# das48.net
KiCad netlist of a schematic drawn in EAGLE
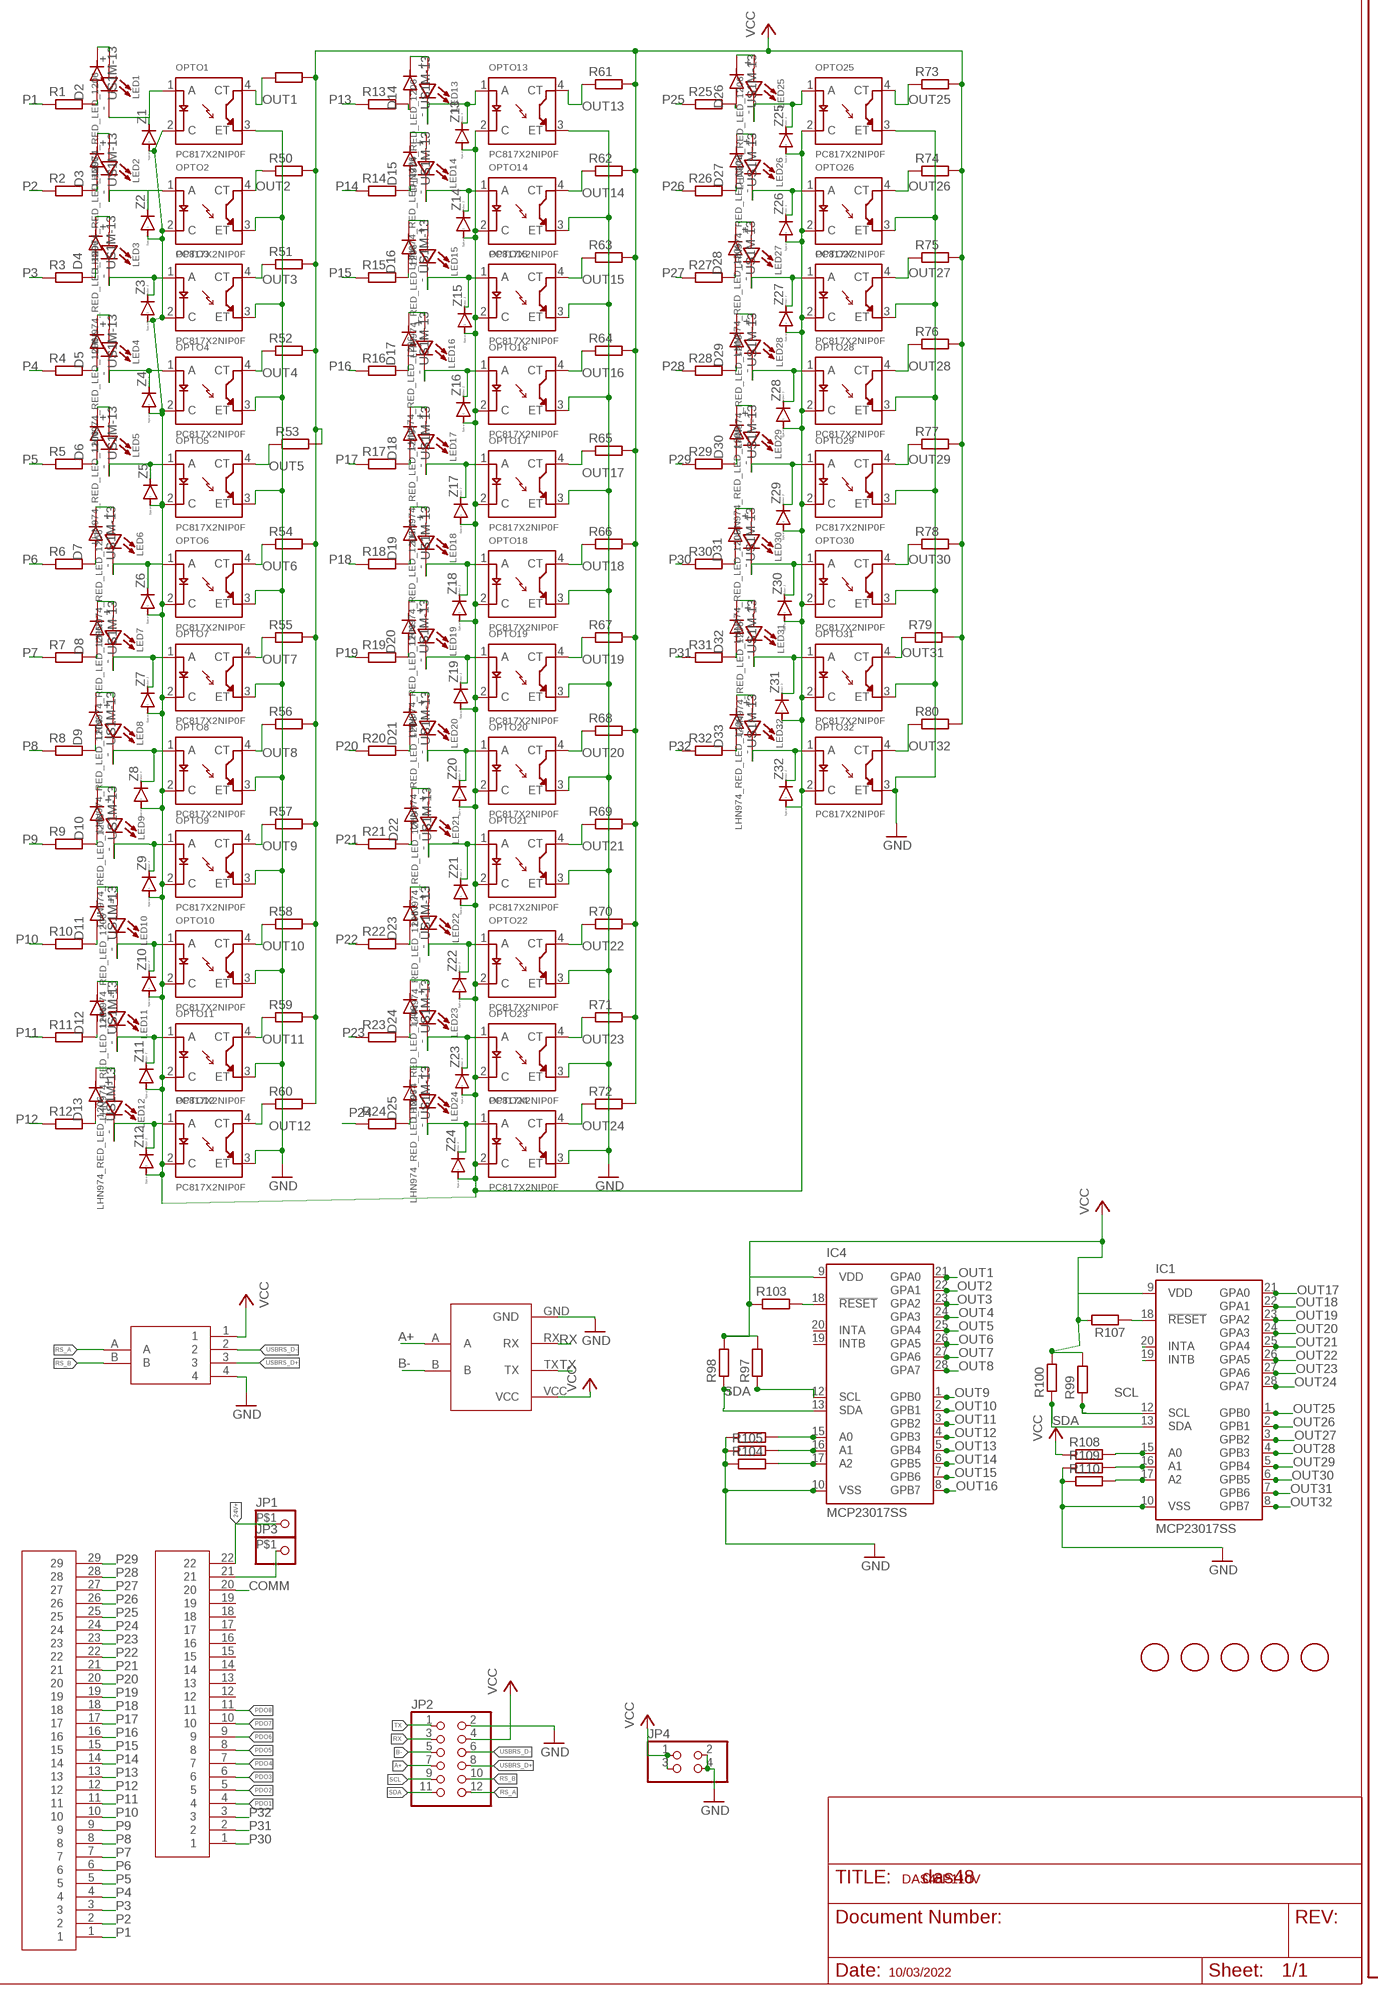
[diagram p0: schematic, sheet 1, part 1 of 2]
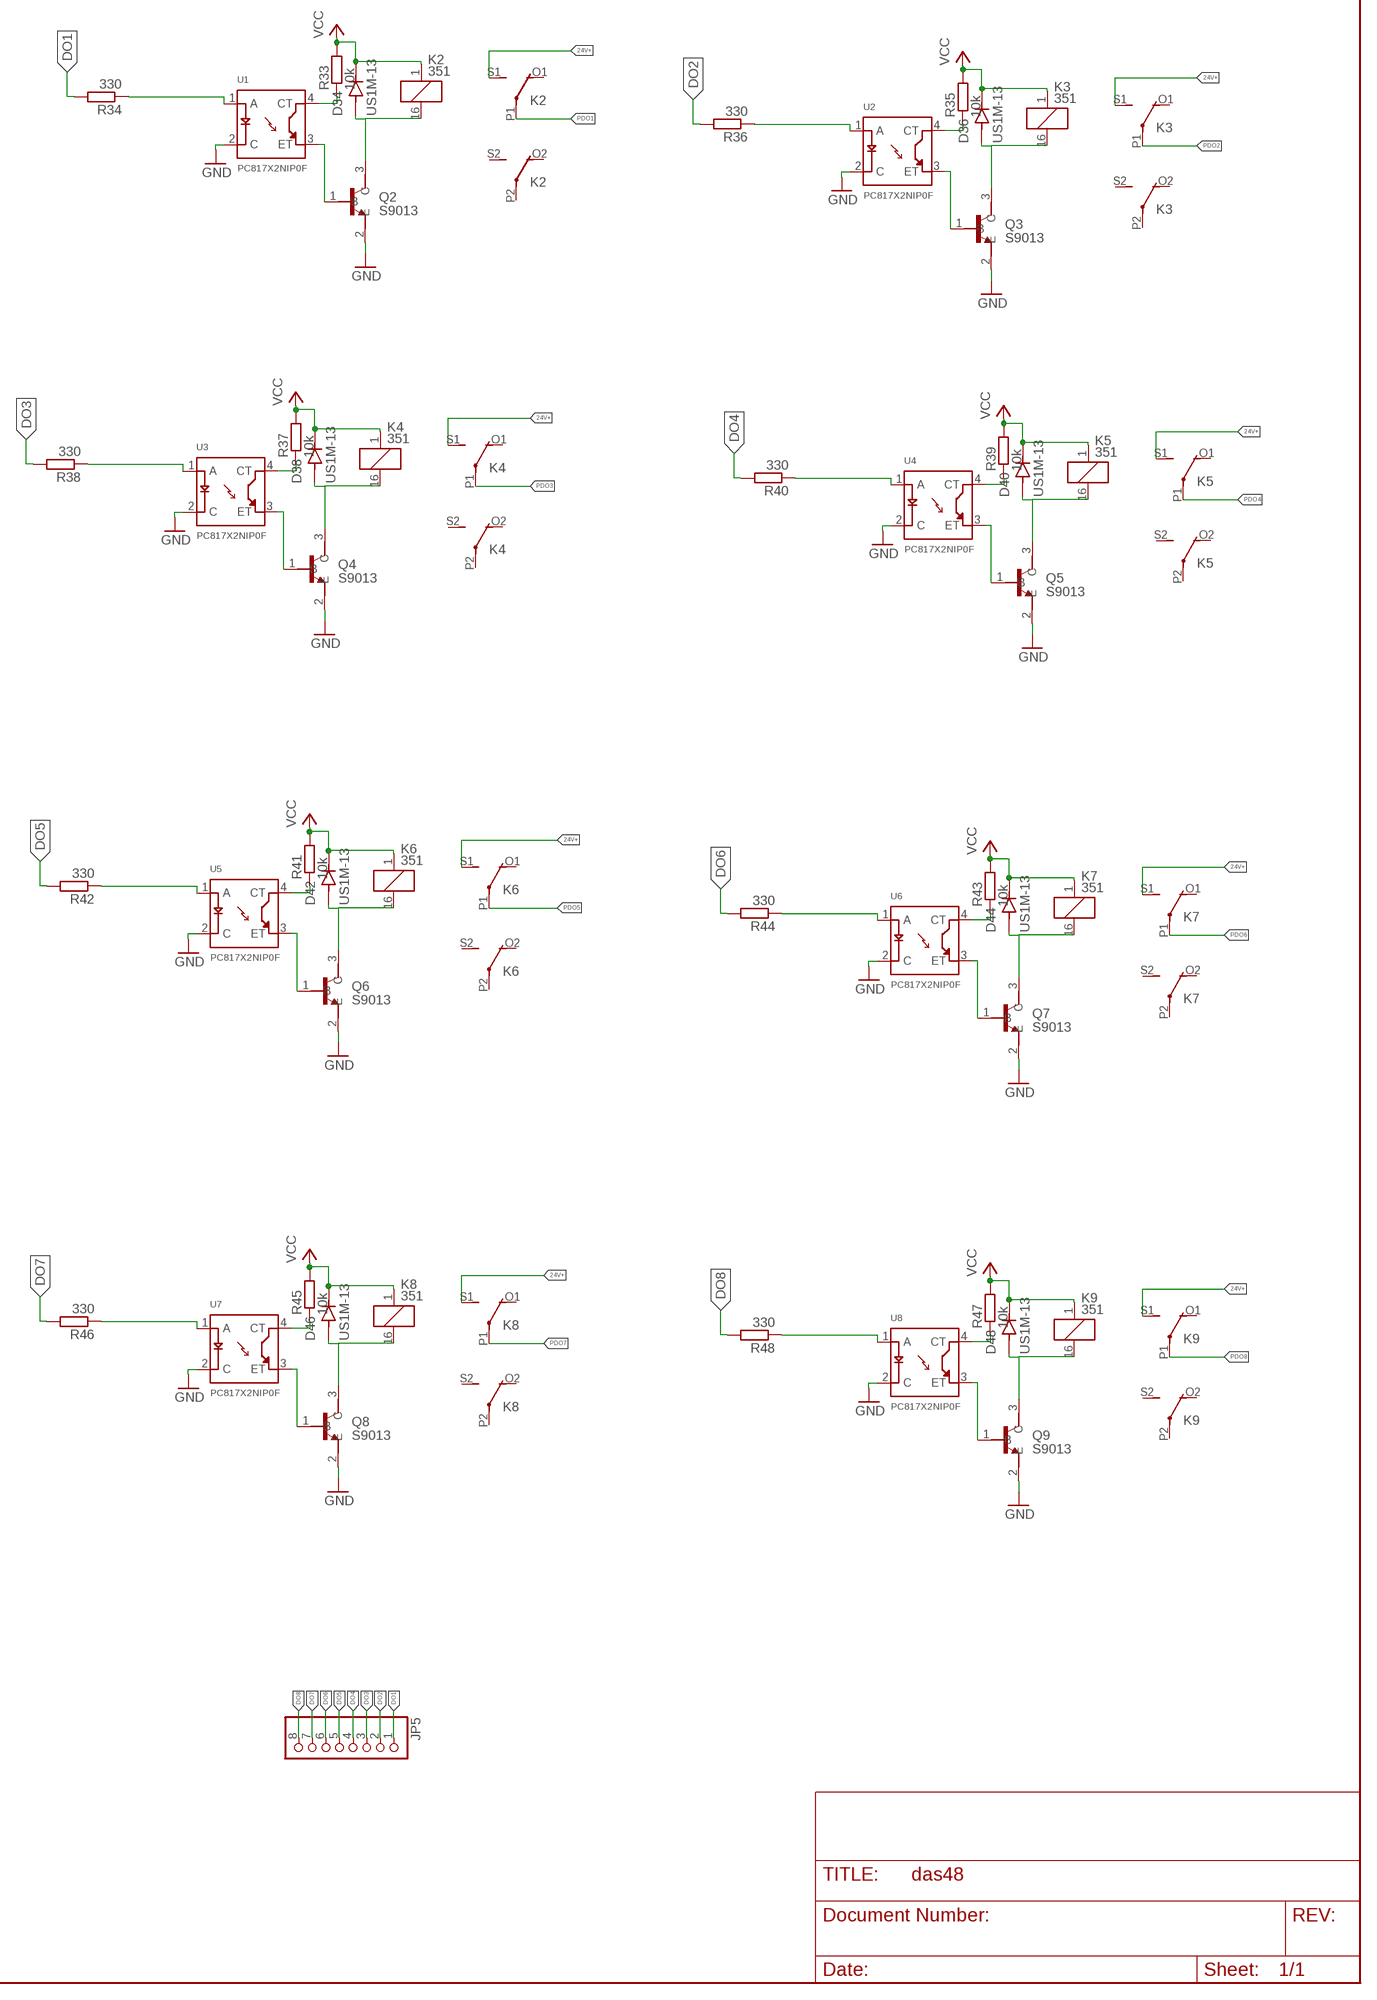
[diagram p1: schematic, sheet 1, part 2 of 2]

(export (version "E")
  (design (tool "Eeschema 10.0.6"))
  (components
    (comp (ref "D2")
      (value "US1M-13")
      (footprint "eagle-import:DIOM5226X240N")
      (fields (field (name "MF") "Diodes Incorporated"))
      (libsource (lib "eagle-import") (part "US1M-13"))
    )
    (comp (ref "D3")
      (value "US1M-13")
      (footprint "eagle-import:DIOM5226X240N")
      (fields (field (name "MF") "Diodes Incorporated"))
      (libsource (lib "eagle-import") (part "US1M-13"))
    )
    (comp (ref "D4")
      (value "US1M-13")
      (footprint "eagle-import:DIOM5226X240N")
      (fields (field (name "MF") "Diodes Incorporated"))
      (libsource (lib "eagle-import") (part "US1M-13"))
    )
    (comp (ref "D5")
      (value "US1M-13")
      (footprint "eagle-import:DIOM5226X240N")
      (fields (field (name "MF") "Diodes Incorporated"))
      (libsource (lib "eagle-import") (part "US1M-13"))
    )
    (comp (ref "D6")
      (value "US1M-13")
      (footprint "eagle-import:DIOM5226X240N")
      (fields (field (name "MF") "Diodes Incorporated"))
      (libsource (lib "eagle-import") (part "US1M-13"))
    )
    (comp (ref "D7")
      (value "US1M-13")
      (footprint "eagle-import:DIOM5226X240N")
      (fields (field (name "MF") "Diodes Incorporated"))
      (libsource (lib "eagle-import") (part "US1M-13"))
    )
    (comp (ref "D8")
      (value "US1M-13")
      (footprint "eagle-import:DIOM5226X240N")
      (fields (field (name "MF") "Diodes Incorporated"))
      (libsource (lib "eagle-import") (part "US1M-13"))
    )
    (comp (ref "D9")
      (value "US1M-13")
      (footprint "eagle-import:DIOM5226X240N")
      (fields (field (name "MF") "Diodes Incorporated"))
      (libsource (lib "eagle-import") (part "US1M-13"))
    )
    (comp (ref "D10")
      (value "US1M-13")
      (footprint "eagle-import:DIOM5226X240N")
      (fields (field (name "MF") "Diodes Incorporated"))
      (libsource (lib "eagle-import") (part "US1M-13"))
    )
    (comp (ref "D11")
      (value "US1M-13")
      (footprint "eagle-import:DIOM5226X240N")
      (fields (field (name "MF") "Diodes Incorporated"))
      (libsource (lib "eagle-import") (part "US1M-13"))
    )
    (comp (ref "D12")
      (value "US1M-13")
      (footprint "eagle-import:DIOM5226X240N")
      (fields (field (name "MF") "Diodes Incorporated"))
      (libsource (lib "eagle-import") (part "US1M-13"))
    )
    (comp (ref "D13")
      (value "US1M-13")
      (footprint "eagle-import:DIOM5226X240N")
      (fields (field (name "MF") "Diodes Incorporated"))
      (libsource (lib "eagle-import") (part "US1M-13"))
    )
    (comp (ref "D14")
      (value "US1M-13")
      (footprint "eagle-import:DIOM5226X240N")
      (fields (field (name "MF") "Diodes Incorporated"))
      (libsource (lib "eagle-import") (part "US1M-13"))
    )
    (comp (ref "D15")
      (value "US1M-13")
      (footprint "eagle-import:DIOM5226X240N")
      (fields (field (name "MF") "Diodes Incorporated"))
      (libsource (lib "eagle-import") (part "US1M-13"))
    )
    (comp (ref "D16")
      (value "US1M-13")
      (footprint "eagle-import:DIOM5226X240N")
      (fields (field (name "MF") "Diodes Incorporated"))
      (libsource (lib "eagle-import") (part "US1M-13"))
    )
    (comp (ref "D17")
      (value "US1M-13")
      (footprint "eagle-import:DIOM5226X240N")
      (fields (field (name "MF") "Diodes Incorporated"))
      (libsource (lib "eagle-import") (part "US1M-13"))
    )
    (comp (ref "D18")
      (value "US1M-13")
      (footprint "eagle-import:DIOM5226X240N")
      (fields (field (name "MF") "Diodes Incorporated"))
      (libsource (lib "eagle-import") (part "US1M-13"))
    )
    (comp (ref "D19")
      (value "US1M-13")
      (footprint "eagle-import:DIOM5226X240N")
      (fields (field (name "MF") "Diodes Incorporated"))
      (libsource (lib "eagle-import") (part "US1M-13"))
    )
    (comp (ref "D20")
      (value "US1M-13")
      (footprint "eagle-import:DIOM5226X240N")
      (fields (field (name "MF") "Diodes Incorporated"))
      (libsource (lib "eagle-import") (part "US1M-13"))
    )
    (comp (ref "D21")
      (value "US1M-13")
      (footprint "eagle-import:DIOM5226X240N")
      (fields (field (name "MF") "Diodes Incorporated"))
      (libsource (lib "eagle-import") (part "US1M-13"))
    )
    (comp (ref "D22")
      (value "US1M-13")
      (footprint "eagle-import:DIOM5226X240N")
      (fields (field (name "MF") "Diodes Incorporated"))
      (libsource (lib "eagle-import") (part "US1M-13"))
    )
    (comp (ref "D23")
      (value "US1M-13")
      (footprint "eagle-import:DIOM5226X240N")
      (fields (field (name "MF") "Diodes Incorporated"))
      (libsource (lib "eagle-import") (part "US1M-13"))
    )
    (comp (ref "D24")
      (value "US1M-13")
      (footprint "eagle-import:DIOM5226X240N")
      (fields (field (name "MF") "Diodes Incorporated"))
      (libsource (lib "eagle-import") (part "US1M-13"))
    )
    (comp (ref "D25")
      (value "US1M-13")
      (footprint "eagle-import:DIOM5226X240N")
      (fields (field (name "MF") "Diodes Incorporated"))
      (libsource (lib "eagle-import") (part "US1M-13"))
    )
    (comp (ref "D26")
      (value "US1M-13")
      (footprint "eagle-import:DIOM5226X240N")
      (fields (field (name "MF") "Diodes Incorporated"))
      (libsource (lib "eagle-import") (part "US1M-13"))
    )
    (comp (ref "D27")
      (value "US1M-13")
      (footprint "eagle-import:DIOM5226X240N")
      (fields (field (name "MF") "Diodes Incorporated"))
      (libsource (lib "eagle-import") (part "US1M-13"))
    )
    (comp (ref "D28")
      (value "US1M-13")
      (footprint "eagle-import:DIOM5226X240N")
      (fields (field (name "MF") "Diodes Incorporated"))
      (libsource (lib "eagle-import") (part "US1M-13"))
    )
    (comp (ref "D29")
      (value "US1M-13")
      (footprint "eagle-import:DIOM5226X240N")
      (fields (field (name "MF") "Diodes Incorporated"))
      (libsource (lib "eagle-import") (part "US1M-13"))
    )
    (comp (ref "D30")
      (value "US1M-13")
      (footprint "eagle-import:DIOM5226X240N")
      (fields (field (name "MF") "Diodes Incorporated"))
      (libsource (lib "eagle-import") (part "US1M-13"))
    )
    (comp (ref "D31")
      (value "US1M-13")
      (footprint "eagle-import:DIOM5226X240N")
      (fields (field (name "MF") "Diodes Incorporated"))
      (libsource (lib "eagle-import") (part "US1M-13"))
    )
    (comp (ref "D32")
      (value "US1M-13")
      (footprint "eagle-import:DIOM5226X240N")
      (fields (field (name "MF") "Diodes Incorporated"))
      (libsource (lib "eagle-import") (part "US1M-13"))
    )
    (comp (ref "D33")
      (value "US1M-13")
      (footprint "eagle-import:DIOM5226X240N")
      (fields (field (name "MF") "Diodes Incorporated"))
      (libsource (lib "eagle-import") (part "US1M-13"))
    )
    (comp (ref "D34")
      (value "US1M-13")
      (footprint "eagle-import:DIOM5226X240N")
      (fields (field (name "MF") "Diodes Incorporated"))
      (libsource (lib "eagle-import") (part "US1M-13"))
    )
    (comp (ref "D36")
      (value "US1M-13")
      (footprint "eagle-import:DIOM5226X240N")
      (fields (field (name "MF") "Diodes Incorporated"))
      (libsource (lib "eagle-import") (part "US1M-13"))
    )
    (comp (ref "D38")
      (value "US1M-13")
      (footprint "eagle-import:DIOM5226X240N")
      (fields (field (name "MF") "Diodes Incorporated"))
      (libsource (lib "eagle-import") (part "US1M-13"))
    )
    (comp (ref "D40")
      (value "US1M-13")
      (footprint "eagle-import:DIOM5226X240N")
      (fields (field (name "MF") "Diodes Incorporated"))
      (libsource (lib "eagle-import") (part "US1M-13"))
    )
    (comp (ref "D42")
      (value "US1M-13")
      (footprint "eagle-import:DIOM5226X240N")
      (fields (field (name "MF") "Diodes Incorporated"))
      (libsource (lib "eagle-import") (part "US1M-13"))
    )
    (comp (ref "D44")
      (value "US1M-13")
      (footprint "eagle-import:DIOM5226X240N")
      (fields (field (name "MF") "Diodes Incorporated"))
      (libsource (lib "eagle-import") (part "US1M-13"))
    )
    (comp (ref "D46")
      (value "US1M-13")
      (footprint "eagle-import:DIOM5226X240N")
      (fields (field (name "MF") "Diodes Incorporated"))
      (libsource (lib "eagle-import") (part "US1M-13"))
    )
    (comp (ref "D48")
      (value "US1M-13")
      (footprint "eagle-import:DIOM5226X240N")
      (fields (field (name "MF") "Diodes Incorporated"))
      (libsource (lib "eagle-import") (part "US1M-13"))
    )
    (comp (ref "HEADER-22P1")
      (value "HEADER-22P")
      (footprint "eagle-import:HEADER-29P")
      (libsource (lib "eagle-import") (part "HEADER-22P"))
    )
    (comp (ref "HEADER-29P1")
      (value "HEADER-29P")
      (footprint "eagle-import:HEADER-29P")
      (libsource (lib "eagle-import") (part "HEADER-29P"))
    )
    (comp (ref "IC1")
      (value "MCP23017SS")
      (footprint "eagle-import:SSOP28DB")
      (libsource (lib "eagle-import") (part "MCP23017SS"))
    )
    (comp (ref "IC4")
      (value "MCP23017SS")
      (footprint "eagle-import:SSOP28DB")
      (libsource (lib "eagle-import") (part "MCP23017SS"))
    )
    (comp (ref "JP1")
      (value "PINHD-1X1-BIGPOGO")
      (footprint "eagle-import:1X1-BIGPOGO")
      (libsource (lib "eagle-import") (part "PINHD-1X1-BIGPOGO"))
    )
    (comp (ref "JP2")
      (value "PINHD-2X6")
      (footprint "eagle-import:2X06")
      (libsource (lib "eagle-import") (part "PINHD-2X6"))
    )
    (comp (ref "JP3")
      (value "PINHD-1X1-BIGPOGO")
      (footprint "eagle-import:1X1-BIGPOGO")
      (libsource (lib "eagle-import") (part "PINHD-1X1-BIGPOGO"))
    )
    (comp (ref "JP4")
      (value "PINHD-2X2")
      (footprint "eagle-import:2X02")
      (libsource (lib "eagle-import") (part "PINHD-2X2"))
    )
    (comp (ref "JP5")
      (value "PINHD-1X8")
      (footprint "eagle-import:1X08")
      (libsource (lib "eagle-import") (part "PINHD-1X8"))
    )
    (comp (ref "K2")
      (value "351")
      (footprint "eagle-import:351")
      (libsource (lib "eagle-import") (part "351"))
    )
    (comp (ref "K3")
      (value "351")
      (footprint "eagle-import:351")
      (libsource (lib "eagle-import") (part "351"))
    )
    (comp (ref "K4")
      (value "351")
      (footprint "eagle-import:351")
      (libsource (lib "eagle-import") (part "351"))
    )
    (comp (ref "K5")
      (value "351")
      (footprint "eagle-import:351")
      (libsource (lib "eagle-import") (part "351"))
    )
    (comp (ref "K6")
      (value "351")
      (footprint "eagle-import:351")
      (libsource (lib "eagle-import") (part "351"))
    )
    (comp (ref "K7")
      (value "351")
      (footprint "eagle-import:351")
      (libsource (lib "eagle-import") (part "351"))
    )
    (comp (ref "K8")
      (value "351")
      (footprint "eagle-import:351")
      (libsource (lib "eagle-import") (part "351"))
    )
    (comp (ref "K9")
      (value "351")
      (footprint "eagle-import:351")
      (libsource (lib "eagle-import") (part "351"))
    )
    (comp (ref "LED1")
      (value "LHN974_RED_LED_1206")
      (footprint "eagle-import:LEDC3216X120N")
      (fields (field (name "MF") "Osram") (field (name "MP") "LHN974 RED LED 1206"))
      (libsource (lib "eagle-import") (part "LHN974_RED_LED_1206"))
    )
    (comp (ref "LED2")
      (value "LHN974_RED_LED_1206")
      (footprint "eagle-import:LEDC3216X120N")
      (fields (field (name "MF") "Osram") (field (name "MP") "LHN974 RED LED 1206"))
      (libsource (lib "eagle-import") (part "LHN974_RED_LED_1206"))
    )
    (comp (ref "LED3")
      (value "LHN974_RED_LED_1206")
      (footprint "eagle-import:LEDC3216X120N")
      (fields (field (name "MF") "Osram") (field (name "MP") "LHN974 RED LED 1206"))
      (libsource (lib "eagle-import") (part "LHN974_RED_LED_1206"))
    )
    (comp (ref "LED4")
      (value "LHN974_RED_LED_1206")
      (footprint "eagle-import:LEDC3216X120N")
      (fields (field (name "MF") "Osram") (field (name "MP") "LHN974 RED LED 1206"))
      (libsource (lib "eagle-import") (part "LHN974_RED_LED_1206"))
    )
    (comp (ref "LED5")
      (value "LHN974_RED_LED_1206")
      (footprint "eagle-import:LEDC3216X120N")
      (fields (field (name "MF") "Osram") (field (name "MP") "LHN974 RED LED 1206"))
      (libsource (lib "eagle-import") (part "LHN974_RED_LED_1206"))
    )
    (comp (ref "LED6")
      (value "LHN974_RED_LED_1206")
      (footprint "eagle-import:LEDC3216X120N")
      (fields (field (name "MF") "Osram") (field (name "MP") "LHN974 RED LED 1206"))
      (libsource (lib "eagle-import") (part "LHN974_RED_LED_1206"))
    )
    (comp (ref "LED7")
      (value "LHN974_RED_LED_1206")
      (footprint "eagle-import:LEDC3216X120N")
      (fields (field (name "MF") "Osram") (field (name "MP") "LHN974 RED LED 1206"))
      (libsource (lib "eagle-import") (part "LHN974_RED_LED_1206"))
    )
    (comp (ref "LED8")
      (value "LHN974_RED_LED_1206")
      (footprint "eagle-import:LEDC3216X120N")
      (fields (field (name "MF") "Osram") (field (name "MP") "LHN974 RED LED 1206"))
      (libsource (lib "eagle-import") (part "LHN974_RED_LED_1206"))
    )
    (comp (ref "LED9")
      (value "LHN974_RED_LED_1206")
      (footprint "eagle-import:LEDC3216X120N")
      (fields (field (name "MF") "Osram") (field (name "MP") "LHN974 RED LED 1206"))
      (libsource (lib "eagle-import") (part "LHN974_RED_LED_1206"))
    )
    (comp (ref "LED10")
      (value "LHN974_RED_LED_1206")
      (footprint "eagle-import:LEDC3216X120N")
      (fields (field (name "MF") "Osram") (field (name "MP") "LHN974 RED LED 1206"))
      (libsource (lib "eagle-import") (part "LHN974_RED_LED_1206"))
    )
    (comp (ref "LED11")
      (value "LHN974_RED_LED_1206")
      (footprint "eagle-import:LEDC3216X120N")
      (fields (field (name "MF") "Osram") (field (name "MP") "LHN974 RED LED 1206"))
      (libsource (lib "eagle-import") (part "LHN974_RED_LED_1206"))
    )
    (comp (ref "LED12")
      (value "LHN974_RED_LED_1206")
      (footprint "eagle-import:LEDC3216X120N")
      (fields (field (name "MF") "Osram") (field (name "MP") "LHN974 RED LED 1206"))
      (libsource (lib "eagle-import") (part "LHN974_RED_LED_1206"))
    )
    (comp (ref "LED13")
      (value "LHN974_RED_LED_1206")
      (footprint "eagle-import:LEDC3216X120N")
      (fields (field (name "MF") "Osram") (field (name "MP") "LHN974 RED LED 1206"))
      (libsource (lib "eagle-import") (part "LHN974_RED_LED_1206"))
    )
    (comp (ref "LED14")
      (value "LHN974_RED_LED_1206")
      (footprint "eagle-import:LEDC3216X120N")
      (fields (field (name "MF") "Osram") (field (name "MP") "LHN974 RED LED 1206"))
      (libsource (lib "eagle-import") (part "LHN974_RED_LED_1206"))
    )
    (comp (ref "LED15")
      (value "LHN974_RED_LED_1206")
      (footprint "eagle-import:LEDC3216X120N")
      (fields (field (name "MF") "Osram") (field (name "MP") "LHN974 RED LED 1206"))
      (libsource (lib "eagle-import") (part "LHN974_RED_LED_1206"))
    )
    (comp (ref "LED16")
      (value "LHN974_RED_LED_1206")
      (footprint "eagle-import:LEDC3216X120N")
      (fields (field (name "MF") "Osram") (field (name "MP") "LHN974 RED LED 1206"))
      (libsource (lib "eagle-import") (part "LHN974_RED_LED_1206"))
    )
    (comp (ref "LED17")
      (value "LHN974_RED_LED_1206")
      (footprint "eagle-import:LEDC3216X120N")
      (fields (field (name "MF") "Osram") (field (name "MP") "LHN974 RED LED 1206"))
      (libsource (lib "eagle-import") (part "LHN974_RED_LED_1206"))
    )
    (comp (ref "LED18")
      (value "LHN974_RED_LED_1206")
      (footprint "eagle-import:LEDC3216X120N")
      (fields (field (name "MF") "Osram") (field (name "MP") "LHN974 RED LED 1206"))
      (libsource (lib "eagle-import") (part "LHN974_RED_LED_1206"))
    )
    (comp (ref "LED19")
      (value "LHN974_RED_LED_1206")
      (footprint "eagle-import:LEDC3216X120N")
      (fields (field (name "MF") "Osram") (field (name "MP") "LHN974 RED LED 1206"))
      (libsource (lib "eagle-import") (part "LHN974_RED_LED_1206"))
    )
    (comp (ref "LED20")
      (value "LHN974_RED_LED_1206")
      (footprint "eagle-import:LEDC3216X120N")
      (fields (field (name "MF") "Osram") (field (name "MP") "LHN974 RED LED 1206"))
      (libsource (lib "eagle-import") (part "LHN974_RED_LED_1206"))
    )
    (comp (ref "LED21")
      (value "LHN974_RED_LED_1206")
      (footprint "eagle-import:LEDC3216X120N")
      (fields (field (name "MF") "Osram") (field (name "MP") "LHN974 RED LED 1206"))
      (libsource (lib "eagle-import") (part "LHN974_RED_LED_1206"))
    )
    (comp (ref "LED22")
      (value "LHN974_RED_LED_1206")
      (footprint "eagle-import:LEDC3216X120N")
      (fields (field (name "MF") "Osram") (field (name "MP") "LHN974 RED LED 1206"))
      (libsource (lib "eagle-import") (part "LHN974_RED_LED_1206"))
    )
    (comp (ref "LED23")
      (value "LHN974_RED_LED_1206")
      (footprint "eagle-import:LEDC3216X120N")
      (fields (field (name "MF") "Osram") (field (name "MP") "LHN974 RED LED 1206"))
      (libsource (lib "eagle-import") (part "LHN974_RED_LED_1206"))
    )
    (comp (ref "LED24")
      (value "LHN974_RED_LED_1206")
      (footprint "eagle-import:LEDC3216X120N")
      (fields (field (name "MF") "Osram") (field (name "MP") "LHN974 RED LED 1206"))
      (libsource (lib "eagle-import") (part "LHN974_RED_LED_1206"))
    )
    (comp (ref "LED25")
      (value "LHN974_RED_LED_1206")
      (footprint "eagle-import:LEDC3216X120N")
      (fields (field (name "MF") "Osram") (field (name "MP") "LHN974 RED LED 1206"))
      (libsource (lib "eagle-import") (part "LHN974_RED_LED_1206"))
    )
    (comp (ref "LED26")
      (value "LHN974_RED_LED_1206")
      (footprint "eagle-import:LEDC3216X120N")
      (fields (field (name "MF") "Osram") (field (name "MP") "LHN974 RED LED 1206"))
      (libsource (lib "eagle-import") (part "LHN974_RED_LED_1206"))
    )
    (comp (ref "LED27")
      (value "LHN974_RED_LED_1206")
      (footprint "eagle-import:LEDC3216X120N")
      (fields (field (name "MF") "Osram") (field (name "MP") "LHN974 RED LED 1206"))
      (libsource (lib "eagle-import") (part "LHN974_RED_LED_1206"))
    )
    (comp (ref "LED28")
      (value "LHN974_RED_LED_1206")
      (footprint "eagle-import:LEDC3216X120N")
      (fields (field (name "MF") "Osram") (field (name "MP") "LHN974 RED LED 1206"))
      (libsource (lib "eagle-import") (part "LHN974_RED_LED_1206"))
    )
    (comp (ref "LED29")
      (value "LHN974_RED_LED_1206")
      (footprint "eagle-import:LEDC3216X120N")
      (fields (field (name "MF") "Osram") (field (name "MP") "LHN974 RED LED 1206"))
      (libsource (lib "eagle-import") (part "LHN974_RED_LED_1206"))
    )
    (comp (ref "LED30")
      (value "LHN974_RED_LED_1206")
      (footprint "eagle-import:LEDC3216X120N")
      (fields (field (name "MF") "Osram") (field (name "MP") "LHN974 RED LED 1206"))
      (libsource (lib "eagle-import") (part "LHN974_RED_LED_1206"))
    )
    (comp (ref "LED31")
      (value "LHN974_RED_LED_1206")
      (footprint "eagle-import:LEDC3216X120N")
      (fields (field (name "MF") "Osram") (field (name "MP") "LHN974 RED LED 1206"))
      (libsource (lib "eagle-import") (part "LHN974_RED_LED_1206"))
    )
    (comp (ref "LED32")
      (value "LHN974_RED_LED_1206")
      (footprint "eagle-import:LEDC3216X120N")
      (fields (field (name "MF") "Osram") (field (name "MP") "LHN974 RED LED 1206"))
      (libsource (lib "eagle-import") (part "LHN974_RED_LED_1206"))
    )
    (comp (ref "OPTO1")
      (value "PC817X2NIP0F")
      (footprint "eagle-import:SOT254P975X400-4N")
      (fields (field (name "MF") "Sharp Microelectronics"))
      (libsource (lib "eagle-import") (part "PC817X2NIP0F"))
    )
    (comp (ref "OPTO2")
      (value "PC817X2NIP0F")
      (footprint "eagle-import:SOT254P975X400-4N")
      (fields (field (name "MF") "Sharp Microelectronics"))
      (libsource (lib "eagle-import") (part "PC817X2NIP0F"))
    )
    (comp (ref "OPTO3")
      (value "PC817X2NIP0F")
      (footprint "eagle-import:SOT254P975X400-4N")
      (fields (field (name "MF") "Sharp Microelectronics"))
      (libsource (lib "eagle-import") (part "PC817X2NIP0F"))
    )
    (comp (ref "OPTO4")
      (value "PC817X2NIP0F")
      (footprint "eagle-import:SOT254P975X400-4N")
      (fields (field (name "MF") "Sharp Microelectronics"))
      (libsource (lib "eagle-import") (part "PC817X2NIP0F"))
    )
    (comp (ref "OPTO5")
      (value "PC817X2NIP0F")
      (footprint "eagle-import:SOT254P975X400-4N")
      (fields (field (name "MF") "Sharp Microelectronics"))
      (libsource (lib "eagle-import") (part "PC817X2NIP0F"))
    )
    (comp (ref "OPTO6")
      (value "PC817X2NIP0F")
      (footprint "eagle-import:SOT254P975X400-4N")
      (fields (field (name "MF") "Sharp Microelectronics"))
      (libsource (lib "eagle-import") (part "PC817X2NIP0F"))
    )
    (comp (ref "OPTO7")
      (value "PC817X2NIP0F")
      (footprint "eagle-import:SOT254P975X400-4N")
      (fields (field (name "MF") "Sharp Microelectronics"))
      (libsource (lib "eagle-import") (part "PC817X2NIP0F"))
    )
    (comp (ref "OPTO8")
      (value "PC817X2NIP0F")
      (footprint "eagle-import:SOT254P975X400-4N")
      (fields (field (name "MF") "Sharp Microelectronics"))
      (libsource (lib "eagle-import") (part "PC817X2NIP0F"))
    )
    (comp (ref "OPTO9")
      (value "PC817X2NIP0F")
      (footprint "eagle-import:SOT254P975X400-4N")
      (fields (field (name "MF") "Sharp Microelectronics"))
      (libsource (lib "eagle-import") (part "PC817X2NIP0F"))
    )
    (comp (ref "OPTO10")
      (value "PC817X2NIP0F")
      (footprint "eagle-import:SOT254P975X400-4N")
      (fields (field (name "MF") "Sharp Microelectronics"))
      (libsource (lib "eagle-import") (part "PC817X2NIP0F"))
    )
    (comp (ref "OPTO11")
      (value "PC817X2NIP0F")
      (footprint "eagle-import:SOT254P975X400-4N")
      (fields (field (name "MF") "Sharp Microelectronics"))
      (libsource (lib "eagle-import") (part "PC817X2NIP0F"))
    )
    (comp (ref "OPTO12")
      (value "PC817X2NIP0F")
      (footprint "eagle-import:SOT254P975X400-4N")
      (fields (field (name "MF") "Sharp Microelectronics"))
      (libsource (lib "eagle-import") (part "PC817X2NIP0F"))
    )
    (comp (ref "OPTO13")
      (value "PC817X2NIP0F")
      (footprint "eagle-import:SOT254P975X400-4N")
      (fields (field (name "MF") "Sharp Microelectronics"))
      (libsource (lib "eagle-import") (part "PC817X2NIP0F"))
    )
    (comp (ref "OPTO14")
      (value "PC817X2NIP0F")
      (footprint "eagle-import:SOT254P975X400-4N")
      (fields (field (name "MF") "Sharp Microelectronics"))
      (libsource (lib "eagle-import") (part "PC817X2NIP0F"))
    )
    (comp (ref "OPTO15")
      (value "PC817X2NIP0F")
      (footprint "eagle-import:SOT254P975X400-4N")
      (fields (field (name "MF") "Sharp Microelectronics"))
      (libsource (lib "eagle-import") (part "PC817X2NIP0F"))
    )
    (comp (ref "OPTO16")
      (value "PC817X2NIP0F")
      (footprint "eagle-import:SOT254P975X400-4N")
      (fields (field (name "MF") "Sharp Microelectronics"))
      (libsource (lib "eagle-import") (part "PC817X2NIP0F"))
    )
    (comp (ref "OPTO17")
      (value "PC817X2NIP0F")
      (footprint "eagle-import:SOT254P975X400-4N")
      (fields (field (name "MF") "Sharp Microelectronics"))
      (libsource (lib "eagle-import") (part "PC817X2NIP0F"))
    )
    (comp (ref "OPTO18")
      (value "PC817X2NIP0F")
      (footprint "eagle-import:SOT254P975X400-4N")
      (fields (field (name "MF") "Sharp Microelectronics"))
      (libsource (lib "eagle-import") (part "PC817X2NIP0F"))
    )
    (comp (ref "OPTO19")
      (value "PC817X2NIP0F")
      (footprint "eagle-import:SOT254P975X400-4N")
      (fields (field (name "MF") "Sharp Microelectronics"))
      (libsource (lib "eagle-import") (part "PC817X2NIP0F"))
    )
    (comp (ref "OPTO20")
      (value "PC817X2NIP0F")
      (footprint "eagle-import:SOT254P975X400-4N")
      (fields (field (name "MF") "Sharp Microelectronics"))
      (libsource (lib "eagle-import") (part "PC817X2NIP0F"))
    )
    (comp (ref "OPTO21")
      (value "PC817X2NIP0F")
      (footprint "eagle-import:SOT254P975X400-4N")
      (fields (field (name "MF") "Sharp Microelectronics"))
      (libsource (lib "eagle-import") (part "PC817X2NIP0F"))
    )
    (comp (ref "OPTO22")
      (value "PC817X2NIP0F")
      (footprint "eagle-import:SOT254P975X400-4N")
      (fields (field (name "MF") "Sharp Microelectronics"))
      (libsource (lib "eagle-import") (part "PC817X2NIP0F"))
    )
    (comp (ref "OPTO23")
      (value "PC817X2NIP0F")
      (footprint "eagle-import:SOT254P975X400-4N")
      (fields (field (name "MF") "Sharp Microelectronics"))
      (libsource (lib "eagle-import") (part "PC817X2NIP0F"))
    )
    (comp (ref "OPTO24")
      (value "PC817X2NIP0F")
      (footprint "eagle-import:SOT254P975X400-4N")
      (fields (field (name "MF") "Sharp Microelectronics"))
      (libsource (lib "eagle-import") (part "PC817X2NIP0F"))
    )
    (comp (ref "OPTO25")
      (value "PC817X2NIP0F")
      (footprint "eagle-import:SOT254P975X400-4N")
      (fields (field (name "MF") "Sharp Microelectronics"))
      (libsource (lib "eagle-import") (part "PC817X2NIP0F"))
    )
    (comp (ref "OPTO26")
      (value "PC817X2NIP0F")
      (footprint "eagle-import:SOT254P975X400-4N")
      (fields (field (name "MF") "Sharp Microelectronics"))
      (libsource (lib "eagle-import") (part "PC817X2NIP0F"))
    )
    (comp (ref "OPTO27")
      (value "PC817X2NIP0F")
      (footprint "eagle-import:SOT254P975X400-4N")
      (fields (field (name "MF") "Sharp Microelectronics"))
      (libsource (lib "eagle-import") (part "PC817X2NIP0F"))
    )
    (comp (ref "OPTO28")
      (value "PC817X2NIP0F")
      (footprint "eagle-import:SOT254P975X400-4N")
      (fields (field (name "MF") "Sharp Microelectronics"))
      (libsource (lib "eagle-import") (part "PC817X2NIP0F"))
    )
    (comp (ref "OPTO29")
      (value "PC817X2NIP0F")
      (footprint "eagle-import:SOT254P975X400-4N")
      (fields (field (name "MF") "Sharp Microelectronics"))
      (libsource (lib "eagle-import") (part "PC817X2NIP0F"))
    )
    (comp (ref "OPTO30")
      (value "PC817X2NIP0F")
      (footprint "eagle-import:SOT254P975X400-4N")
      (fields (field (name "MF") "Sharp Microelectronics"))
      (libsource (lib "eagle-import") (part "PC817X2NIP0F"))
    )
    (comp (ref "OPTO31")
      (value "PC817X2NIP0F")
      (footprint "eagle-import:SOT254P975X400-4N")
      (fields (field (name "MF") "Sharp Microelectronics"))
      (libsource (lib "eagle-import") (part "PC817X2NIP0F"))
    )
    (comp (ref "OPTO32")
      (value "PC817X2NIP0F")
      (footprint "eagle-import:SOT254P975X400-4N")
      (fields (field (name "MF") "Sharp Microelectronics"))
      (libsource (lib "eagle-import") (part "PC817X2NIP0F"))
    )
    (comp (ref "Q2")
      (value "S9013")
      (footprint "eagle-import:SOT95P240X120-3N")
      (fields (field (name "MF") "JCET"))
      (libsource (lib "eagle-import") (part "S9013"))
    )
    (comp (ref "Q3")
      (value "S9013")
      (footprint "eagle-import:SOT95P240X120-3N")
      (fields (field (name "MF") "JCET"))
      (libsource (lib "eagle-import") (part "S9013"))
    )
    (comp (ref "Q4")
      (value "S9013")
      (footprint "eagle-import:SOT95P240X120-3N")
      (fields (field (name "MF") "JCET"))
      (libsource (lib "eagle-import") (part "S9013"))
    )
    (comp (ref "Q5")
      (value "S9013")
      (footprint "eagle-import:SOT95P240X120-3N")
      (fields (field (name "MF") "JCET"))
      (libsource (lib "eagle-import") (part "S9013"))
    )
    (comp (ref "Q6")
      (value "S9013")
      (footprint "eagle-import:SOT95P240X120-3N")
      (fields (field (name "MF") "JCET"))
      (libsource (lib "eagle-import") (part "S9013"))
    )
    (comp (ref "Q7")
      (value "S9013")
      (footprint "eagle-import:SOT95P240X120-3N")
      (fields (field (name "MF") "JCET"))
      (libsource (lib "eagle-import") (part "S9013"))
    )
    (comp (ref "Q8")
      (value "S9013")
      (footprint "eagle-import:SOT95P240X120-3N")
      (fields (field (name "MF") "JCET"))
      (libsource (lib "eagle-import") (part "S9013"))
    )
    (comp (ref "Q9")
      (value "S9013")
      (footprint "eagle-import:SOT95P240X120-3N")
      (fields (field (name "MF") "JCET"))
      (libsource (lib "eagle-import") (part "S9013"))
    )
    (comp (ref "R1")
      (value "R-EU_0617/17")
      (footprint "eagle-import:0617_17")
      (libsource (lib "eagle-import") (part "R-EU_0617/17"))
    )
    (comp (ref "R2")
      (value "R-EU_0617/17")
      (footprint "eagle-import:0617_17")
      (libsource (lib "eagle-import") (part "R-EU_0617/17"))
    )
    (comp (ref "R3")
      (value "R-EU_0617/17")
      (footprint "eagle-import:0617_17")
      (libsource (lib "eagle-import") (part "R-EU_0617/17"))
    )
    (comp (ref "R4")
      (value "R-EU_0617/17")
      (footprint "eagle-import:0617_17")
      (libsource (lib "eagle-import") (part "R-EU_0617/17"))
    )
    (comp (ref "R5")
      (value "R-EU_0617/17")
      (footprint "eagle-import:0617_17")
      (libsource (lib "eagle-import") (part "R-EU_0617/17"))
    )
    (comp (ref "R6")
      (value "R-EU_0617/17")
      (footprint "eagle-import:0617_17")
      (libsource (lib "eagle-import") (part "R-EU_0617/17"))
    )
    (comp (ref "R7")
      (value "R-EU_0617/17")
      (footprint "eagle-import:0617_17")
      (libsource (lib "eagle-import") (part "R-EU_0617/17"))
    )
    (comp (ref "R8")
      (value "R-EU_0617/17")
      (footprint "eagle-import:0617_17")
      (libsource (lib "eagle-import") (part "R-EU_0617/17"))
    )
    (comp (ref "R9")
      (value "R-EU_0617/17")
      (footprint "eagle-import:0617_17")
      (libsource (lib "eagle-import") (part "R-EU_0617/17"))
    )
    (comp (ref "R10")
      (value "R-EU_0617/17")
      (footprint "eagle-import:0617_17")
      (libsource (lib "eagle-import") (part "R-EU_0617/17"))
    )
    (comp (ref "R11")
      (value "R-EU_0617/17")
      (footprint "eagle-import:0617_17")
      (libsource (lib "eagle-import") (part "R-EU_0617/17"))
    )
    (comp (ref "R12")
      (value "R-EU_0617/17")
      (footprint "eagle-import:0617_17")
      (libsource (lib "eagle-import") (part "R-EU_0617/17"))
    )
    (comp (ref "R13")
      (value "R-EU_0617/17")
      (footprint "eagle-import:0617_17")
      (libsource (lib "eagle-import") (part "R-EU_0617/17"))
    )
    (comp (ref "R14")
      (value "R-EU_0617/17")
      (footprint "eagle-import:0617_17")
      (libsource (lib "eagle-import") (part "R-EU_0617/17"))
    )
    (comp (ref "R15")
      (value "R-EU_0617/17")
      (footprint "eagle-import:0617_17")
      (libsource (lib "eagle-import") (part "R-EU_0617/17"))
    )
    (comp (ref "R16")
      (value "R-EU_0617/17")
      (footprint "eagle-import:0617_17")
      (libsource (lib "eagle-import") (part "R-EU_0617/17"))
    )
    (comp (ref "R17")
      (value "R-EU_0617/17")
      (footprint "eagle-import:0617_17")
      (libsource (lib "eagle-import") (part "R-EU_0617/17"))
    )
    (comp (ref "R18")
      (value "R-EU_0617/17")
      (footprint "eagle-import:0617_17")
      (libsource (lib "eagle-import") (part "R-EU_0617/17"))
    )
    (comp (ref "R19")
      (value "R-EU_0617/17")
      (footprint "eagle-import:0617_17")
      (libsource (lib "eagle-import") (part "R-EU_0617/17"))
    )
    (comp (ref "R20")
      (value "R-EU_0617/17")
      (footprint "eagle-import:0617_17")
      (libsource (lib "eagle-import") (part "R-EU_0617/17"))
    )
    (comp (ref "R21")
      (value "R-EU_0617/17")
      (footprint "eagle-import:0617_17")
      (libsource (lib "eagle-import") (part "R-EU_0617/17"))
    )
    (comp (ref "R22")
      (value "R-EU_0617/17")
      (footprint "eagle-import:0617_17")
      (libsource (lib "eagle-import") (part "R-EU_0617/17"))
    )
    (comp (ref "R23")
      (value "R-EU_0617/17")
      (footprint "eagle-import:0617_17")
      (libsource (lib "eagle-import") (part "R-EU_0617/17"))
    )
    (comp (ref "R24")
      (value "R-EU_0617/17")
      (footprint "eagle-import:0617_17")
      (libsource (lib "eagle-import") (part "R-EU_0617/17"))
    )
    (comp (ref "R25")
      (value "R-EU_0617/17")
      (footprint "eagle-import:0617_17")
      (libsource (lib "eagle-import") (part "R-EU_0617/17"))
    )
    (comp (ref "R26")
      (value "R-EU_0617/17")
      (footprint "eagle-import:0617_17")
      (libsource (lib "eagle-import") (part "R-EU_0617/17"))
    )
    (comp (ref "R27")
      (value "R-EU_0617/17")
      (footprint "eagle-import:0617_17")
      (libsource (lib "eagle-import") (part "R-EU_0617/17"))
    )
    (comp (ref "R28")
      (value "R-EU_0617/17")
      (footprint "eagle-import:0617_17")
      (libsource (lib "eagle-import") (part "R-EU_0617/17"))
    )
    (comp (ref "R29")
      (value "R-EU_0617/17")
      (footprint "eagle-import:0617_17")
      (libsource (lib "eagle-import") (part "R-EU_0617/17"))
    )
    (comp (ref "R30")
      (value "R-EU_0617/17")
      (footprint "eagle-import:0617_17")
      (libsource (lib "eagle-import") (part "R-EU_0617/17"))
    )
    (comp (ref "R31")
      (value "R-EU_0617/17")
      (footprint "eagle-import:0617_17")
      (libsource (lib "eagle-import") (part "R-EU_0617/17"))
    )
    (comp (ref "R32")
      (value "R-EU_0617/17")
      (footprint "eagle-import:0617_17")
      (libsource (lib "eagle-import") (part "R-EU_0617/17"))
    )
    (comp (ref "R33")
      (value "10k")
      (footprint "eagle-import:R0805")
      (libsource (lib "eagle-import") (part "R-EU_R0805"))
    )
    (comp (ref "R34")
      (value "330")
      (footprint "eagle-import:R0805")
      (libsource (lib "eagle-import") (part "R-EU_R0805"))
    )
    (comp (ref "R35")
      (value "10k")
      (footprint "eagle-import:R0805")
      (libsource (lib "eagle-import") (part "R-EU_R0805"))
    )
    (comp (ref "R36")
      (value "330")
      (footprint "eagle-import:R0805")
      (libsource (lib "eagle-import") (part "R-EU_R0805"))
    )
    (comp (ref "R37")
      (value "10k")
      (footprint "eagle-import:R0805")
      (libsource (lib "eagle-import") (part "R-EU_R0805"))
    )
    (comp (ref "R38")
      (value "330")
      (footprint "eagle-import:R0805")
      (libsource (lib "eagle-import") (part "R-EU_R0805"))
    )
    (comp (ref "R39")
      (value "10k")
      (footprint "eagle-import:R0805")
      (libsource (lib "eagle-import") (part "R-EU_R0805"))
    )
    (comp (ref "R40")
      (value "330")
      (footprint "eagle-import:R0805")
      (libsource (lib "eagle-import") (part "R-EU_R0805"))
    )
    (comp (ref "R41")
      (value "10k")
      (footprint "eagle-import:R0805")
      (libsource (lib "eagle-import") (part "R-EU_R0805"))
    )
    (comp (ref "R42")
      (value "330")
      (footprint "eagle-import:R0805")
      (libsource (lib "eagle-import") (part "R-EU_R0805"))
    )
    (comp (ref "R43")
      (value "10k")
      (footprint "eagle-import:R0805")
      (libsource (lib "eagle-import") (part "R-EU_R0805"))
    )
    (comp (ref "R44")
      (value "330")
      (footprint "eagle-import:R0805")
      (libsource (lib "eagle-import") (part "R-EU_R0805"))
    )
    (comp (ref "R45")
      (value "10k")
      (footprint "eagle-import:R0805")
      (libsource (lib "eagle-import") (part "R-EU_R0805"))
    )
    (comp (ref "R46")
      (value "330")
      (footprint "eagle-import:R0805")
      (libsource (lib "eagle-import") (part "R-EU_R0805"))
    )
    (comp (ref "R47")
      (value "10k")
      (footprint "eagle-import:R0805")
      (libsource (lib "eagle-import") (part "R-EU_R0805"))
    )
    (comp (ref "R48")
      (value "330")
      (footprint "eagle-import:R0805")
      (libsource (lib "eagle-import") (part "R-EU_R0805"))
    )
    (comp (ref "R49")
      (value "R-EU_R0805")
      (footprint "eagle-import:R0805")
      (libsource (lib "eagle-import") (part "R-EU_R0805"))
    )
    (comp (ref "R50")
      (value "R-EU_R0805")
      (footprint "eagle-import:R0805")
      (libsource (lib "eagle-import") (part "R-EU_R0805"))
    )
    (comp (ref "R51")
      (value "R-EU_R0805")
      (footprint "eagle-import:R0805")
      (libsource (lib "eagle-import") (part "R-EU_R0805"))
    )
    (comp (ref "R52")
      (value "R-EU_R0805")
      (footprint "eagle-import:R0805")
      (libsource (lib "eagle-import") (part "R-EU_R0805"))
    )
    (comp (ref "R53")
      (value "R-EU_R0805")
      (footprint "eagle-import:R0805")
      (libsource (lib "eagle-import") (part "R-EU_R0805"))
    )
    (comp (ref "R54")
      (value "R-EU_R0805")
      (footprint "eagle-import:R0805")
      (libsource (lib "eagle-import") (part "R-EU_R0805"))
    )
    (comp (ref "R55")
      (value "R-EU_R0805")
      (footprint "eagle-import:R0805")
      (libsource (lib "eagle-import") (part "R-EU_R0805"))
    )
    (comp (ref "R56")
      (value "R-EU_R0805")
      (footprint "eagle-import:R0805")
      (libsource (lib "eagle-import") (part "R-EU_R0805"))
    )
    (comp (ref "R57")
      (value "R-EU_R0805")
      (footprint "eagle-import:R0805")
      (libsource (lib "eagle-import") (part "R-EU_R0805"))
    )
    (comp (ref "R58")
      (value "R-EU_R0805")
      (footprint "eagle-import:R0805")
      (libsource (lib "eagle-import") (part "R-EU_R0805"))
    )
    (comp (ref "R59")
      (value "R-EU_R0805")
      (footprint "eagle-import:R0805")
      (libsource (lib "eagle-import") (part "R-EU_R0805"))
    )
    (comp (ref "R60")
      (value "R-EU_R0805")
      (footprint "eagle-import:R0805")
      (libsource (lib "eagle-import") (part "R-EU_R0805"))
    )
    (comp (ref "R61")
      (value "R-EU_R0805")
      (footprint "eagle-import:R0805")
      (libsource (lib "eagle-import") (part "R-EU_R0805"))
    )
    (comp (ref "R62")
      (value "R-EU_R0805")
      (footprint "eagle-import:R0805")
      (libsource (lib "eagle-import") (part "R-EU_R0805"))
    )
    (comp (ref "R63")
      (value "R-EU_R0805")
      (footprint "eagle-import:R0805")
      (libsource (lib "eagle-import") (part "R-EU_R0805"))
    )
    (comp (ref "R64")
      (value "R-EU_R0805")
      (footprint "eagle-import:R0805")
      (libsource (lib "eagle-import") (part "R-EU_R0805"))
    )
    (comp (ref "R65")
      (value "R-EU_R0805")
      (footprint "eagle-import:R0805")
      (libsource (lib "eagle-import") (part "R-EU_R0805"))
    )
    (comp (ref "R66")
      (value "R-EU_R0805")
      (footprint "eagle-import:R0805")
      (libsource (lib "eagle-import") (part "R-EU_R0805"))
    )
    (comp (ref "R67")
      (value "R-EU_R0805")
      (footprint "eagle-import:R0805")
      (libsource (lib "eagle-import") (part "R-EU_R0805"))
    )
    (comp (ref "R68")
      (value "R-EU_R0805")
      (footprint "eagle-import:R0805")
      (libsource (lib "eagle-import") (part "R-EU_R0805"))
    )
    (comp (ref "R69")
      (value "R-EU_R0805")
      (footprint "eagle-import:R0805")
      (libsource (lib "eagle-import") (part "R-EU_R0805"))
    )
    (comp (ref "R70")
      (value "R-EU_R0805")
      (footprint "eagle-import:R0805")
      (libsource (lib "eagle-import") (part "R-EU_R0805"))
    )
    (comp (ref "R71")
      (value "R-EU_R0805")
      (footprint "eagle-import:R0805")
      (libsource (lib "eagle-import") (part "R-EU_R0805"))
    )
    (comp (ref "R72")
      (value "R-EU_R0805")
      (footprint "eagle-import:R0805")
      (libsource (lib "eagle-import") (part "R-EU_R0805"))
    )
    (comp (ref "R73")
      (value "R-EU_R0805")
      (footprint "eagle-import:R0805")
      (libsource (lib "eagle-import") (part "R-EU_R0805"))
    )
    (comp (ref "R74")
      (value "R-EU_R0805")
      (footprint "eagle-import:R0805")
      (libsource (lib "eagle-import") (part "R-EU_R0805"))
    )
    (comp (ref "R75")
      (value "R-EU_R0805")
      (footprint "eagle-import:R0805")
      (libsource (lib "eagle-import") (part "R-EU_R0805"))
    )
    (comp (ref "R76")
      (value "R-EU_R0805")
      (footprint "eagle-import:R0805")
      (libsource (lib "eagle-import") (part "R-EU_R0805"))
    )
    (comp (ref "R77")
      (value "R-EU_R0805")
      (footprint "eagle-import:R0805")
      (libsource (lib "eagle-import") (part "R-EU_R0805"))
    )
    (comp (ref "R78")
      (value "R-EU_R0805")
      (footprint "eagle-import:R0805")
      (libsource (lib "eagle-import") (part "R-EU_R0805"))
    )
    (comp (ref "R79")
      (value "R-EU_R0805")
      (footprint "eagle-import:R0805")
      (libsource (lib "eagle-import") (part "R-EU_R0805"))
    )
    (comp (ref "R80")
      (value "R-EU_R0805")
      (footprint "eagle-import:R0805")
      (libsource (lib "eagle-import") (part "R-EU_R0805"))
    )
    (comp (ref "R97")
      (value "R-EU_R0805")
      (footprint "eagle-import:R0805")
      (libsource (lib "eagle-import") (part "R-EU_R0805"))
    )
    (comp (ref "R98")
      (value "R-EU_R0805")
      (footprint "eagle-import:R0805")
      (libsource (lib "eagle-import") (part "R-EU_R0805"))
    )
    (comp (ref "R99")
      (value "R-EU_R0805")
      (footprint "eagle-import:R0805")
      (libsource (lib "eagle-import") (part "R-EU_R0805"))
    )
    (comp (ref "R100")
      (value "R-EU_R0805")
      (footprint "eagle-import:R0805")
      (libsource (lib "eagle-import") (part "R-EU_R0805"))
    )
    (comp (ref "R103")
      (value "R-EU_R0805")
      (footprint "eagle-import:R0805")
      (libsource (lib "eagle-import") (part "R-EU_R0805"))
    )
    (comp (ref "R104")
      (value "R-EU_R0805")
      (footprint "eagle-import:R0805")
      (libsource (lib "eagle-import") (part "R-EU_R0805"))
    )
    (comp (ref "R105")
      (value "R-EU_R0805")
      (footprint "eagle-import:R0805")
      (libsource (lib "eagle-import") (part "R-EU_R0805"))
    )
    (comp (ref "R106")
      (value "R-EU_R0805")
      (footprint "eagle-import:R0805")
      (libsource (lib "eagle-import") (part "R-EU_R0805"))
    )
    (comp (ref "R107")
      (value "R-EU_R0805")
      (footprint "eagle-import:R0805")
      (libsource (lib "eagle-import") (part "R-EU_R0805"))
    )
    (comp (ref "R108")
      (value "R-EU_R0805")
      (footprint "eagle-import:R0805")
      (libsource (lib "eagle-import") (part "R-EU_R0805"))
    )
    (comp (ref "R109")
      (value "R-EU_R0805")
      (footprint "eagle-import:R0805")
      (libsource (lib "eagle-import") (part "R-EU_R0805"))
    )
    (comp (ref "R110")
      (value "R-EU_R0805")
      (footprint "eagle-import:R0805")
      (libsource (lib "eagle-import") (part "R-EU_R0805"))
    )
    (comp (ref "TTL-RS1")
      (value "TTL-RS485")
      (footprint "eagle-import:TTL-RS485")
      (libsource (lib "eagle-import") (part "TTL-RS485"))
    )
    (comp (ref "U$1")
      (value "FIDUCIAL")
      (footprint "eagle-import:FIDUCIAL_1MM")
      (libsource (lib "eagle-import") (part "FIDUCIAL"))
    )
    (comp (ref "U$2")
      (value "FIDUCIAL")
      (footprint "eagle-import:FIDUCIAL_1MM")
      (libsource (lib "eagle-import") (part "FIDUCIAL"))
    )
    (comp (ref "U$3")
      (value "FIDUCIAL")
      (footprint "eagle-import:FIDUCIAL_1MM")
      (libsource (lib "eagle-import") (part "FIDUCIAL"))
    )
    (comp (ref "U$4")
      (value "FIDUCIAL")
      (footprint "eagle-import:FIDUCIAL_1MM")
      (libsource (lib "eagle-import") (part "FIDUCIAL"))
    )
    (comp (ref "U$5")
      (value "FIDUCIAL")
      (footprint "eagle-import:FIDUCIAL_1MM")
      (libsource (lib "eagle-import") (part "FIDUCIAL"))
    )
    (comp (ref "U1")
      (value "PC817X2NIP0F")
      (footprint "eagle-import:SOT254P975X400-4N")
      (fields (field (name "MF") "Sharp Microelectronics"))
      (libsource (lib "eagle-import") (part "PC817X2NIP0F"))
    )
    (comp (ref "U2")
      (value "PC817X2NIP0F")
      (footprint "eagle-import:SOT254P975X400-4N")
      (fields (field (name "MF") "Sharp Microelectronics"))
      (libsource (lib "eagle-import") (part "PC817X2NIP0F"))
    )
    (comp (ref "U3")
      (value "PC817X2NIP0F")
      (footprint "eagle-import:SOT254P975X400-4N")
      (fields (field (name "MF") "Sharp Microelectronics"))
      (libsource (lib "eagle-import") (part "PC817X2NIP0F"))
    )
    (comp (ref "U4")
      (value "PC817X2NIP0F")
      (footprint "eagle-import:SOT254P975X400-4N")
      (fields (field (name "MF") "Sharp Microelectronics"))
      (libsource (lib "eagle-import") (part "PC817X2NIP0F"))
    )
    (comp (ref "U5")
      (value "PC817X2NIP0F")
      (footprint "eagle-import:SOT254P975X400-4N")
      (fields (field (name "MF") "Sharp Microelectronics"))
      (libsource (lib "eagle-import") (part "PC817X2NIP0F"))
    )
    (comp (ref "U6")
      (value "PC817X2NIP0F")
      (footprint "eagle-import:SOT254P975X400-4N")
      (fields (field (name "MF") "Sharp Microelectronics"))
      (libsource (lib "eagle-import") (part "PC817X2NIP0F"))
    )
    (comp (ref "U7")
      (value "PC817X2NIP0F")
      (footprint "eagle-import:SOT254P975X400-4N")
      (fields (field (name "MF") "Sharp Microelectronics"))
      (libsource (lib "eagle-import") (part "PC817X2NIP0F"))
    )
    (comp (ref "U8")
      (value "PC817X2NIP0F")
      (footprint "eagle-import:SOT254P975X400-4N")
      (fields (field (name "MF") "Sharp Microelectronics"))
      (libsource (lib "eagle-import") (part "PC817X2NIP0F"))
    )
    (comp (ref "USB2RS1")
      (value "USB2RS485")
      (footprint "eagle-import:USB2RS485")
      (libsource (lib "eagle-import") (part "USB2RS485"))
    )
    (comp (ref "Z1")
      (value "DIODE-SOD123")
      (footprint "eagle-import:SOD123")
      (libsource (lib "eagle-import") (part "DIODE-SOD123"))
    )
    (comp (ref "Z2")
      (value "DIODE-SOD123")
      (footprint "eagle-import:SOD123")
      (libsource (lib "eagle-import") (part "DIODE-SOD123"))
    )
    (comp (ref "Z3")
      (value "DIODE-SOD123")
      (footprint "eagle-import:SOD123")
      (libsource (lib "eagle-import") (part "DIODE-SOD123"))
    )
    (comp (ref "Z4")
      (value "DIODE-SOD123")
      (footprint "eagle-import:SOD123")
      (libsource (lib "eagle-import") (part "DIODE-SOD123"))
    )
    (comp (ref "Z5")
      (value "DIODE-SOD123")
      (footprint "eagle-import:SOD123")
      (libsource (lib "eagle-import") (part "DIODE-SOD123"))
    )
    (comp (ref "Z6")
      (value "DIODE-SOD123")
      (footprint "eagle-import:SOD123")
      (libsource (lib "eagle-import") (part "DIODE-SOD123"))
    )
    (comp (ref "Z7")
      (value "DIODE-SOD123")
      (footprint "eagle-import:SOD123")
      (libsource (lib "eagle-import") (part "DIODE-SOD123"))
    )
    (comp (ref "Z8")
      (value "DIODE-SOD123")
      (footprint "eagle-import:SOD123")
      (libsource (lib "eagle-import") (part "DIODE-SOD123"))
    )
    (comp (ref "Z9")
      (value "DIODE-SOD123")
      (footprint "eagle-import:SOD123")
      (libsource (lib "eagle-import") (part "DIODE-SOD123"))
    )
    (comp (ref "Z10")
      (value "DIODE-SOD123")
      (footprint "eagle-import:SOD123")
      (libsource (lib "eagle-import") (part "DIODE-SOD123"))
    )
    (comp (ref "Z11")
      (value "DIODE-SOD123")
      (footprint "eagle-import:SOD123")
      (libsource (lib "eagle-import") (part "DIODE-SOD123"))
    )
    (comp (ref "Z12")
      (value "DIODE-SOD123")
      (footprint "eagle-import:SOD123")
      (libsource (lib "eagle-import") (part "DIODE-SOD123"))
    )
    (comp (ref "Z13")
      (value "DIODE-SOD123")
      (footprint "eagle-import:SOD123")
      (libsource (lib "eagle-import") (part "DIODE-SOD123"))
    )
    (comp (ref "Z14")
      (value "DIODE-SOD123")
      (footprint "eagle-import:SOD123")
      (libsource (lib "eagle-import") (part "DIODE-SOD123"))
    )
    (comp (ref "Z15")
      (value "DIODE-SOD123")
      (footprint "eagle-import:SOD123")
      (libsource (lib "eagle-import") (part "DIODE-SOD123"))
    )
    (comp (ref "Z16")
      (value "DIODE-SOD123")
      (footprint "eagle-import:SOD123")
      (libsource (lib "eagle-import") (part "DIODE-SOD123"))
    )
    (comp (ref "Z17")
      (value "DIODE-SOD123")
      (footprint "eagle-import:SOD123")
      (libsource (lib "eagle-import") (part "DIODE-SOD123"))
    )
    (comp (ref "Z18")
      (value "DIODE-SOD123")
      (footprint "eagle-import:SOD123")
      (libsource (lib "eagle-import") (part "DIODE-SOD123"))
    )
    (comp (ref "Z19")
      (value "DIODE-SOD123")
      (footprint "eagle-import:SOD123")
      (libsource (lib "eagle-import") (part "DIODE-SOD123"))
    )
    (comp (ref "Z20")
      (value "DIODE-SOD123")
      (footprint "eagle-import:SOD123")
      (libsource (lib "eagle-import") (part "DIODE-SOD123"))
    )
    (comp (ref "Z21")
      (value "DIODE-SOD123")
      (footprint "eagle-import:SOD123")
      (libsource (lib "eagle-import") (part "DIODE-SOD123"))
    )
    (comp (ref "Z22")
      (value "DIODE-SOD123")
      (footprint "eagle-import:SOD123")
      (libsource (lib "eagle-import") (part "DIODE-SOD123"))
    )
    (comp (ref "Z23")
      (value "DIODE-SOD123")
      (footprint "eagle-import:SOD123")
      (libsource (lib "eagle-import") (part "DIODE-SOD123"))
    )
    (comp (ref "Z24")
      (value "DIODE-SOD123")
      (footprint "eagle-import:SOD123")
      (libsource (lib "eagle-import") (part "DIODE-SOD123"))
    )
    (comp (ref "Z25")
      (value "DIODE-SOD123")
      (footprint "eagle-import:SOD123")
      (libsource (lib "eagle-import") (part "DIODE-SOD123"))
    )
    (comp (ref "Z26")
      (value "DIODE-SOD123")
      (footprint "eagle-import:SOD123")
      (libsource (lib "eagle-import") (part "DIODE-SOD123"))
    )
    (comp (ref "Z27")
      (value "DIODE-SOD123")
      (footprint "eagle-import:SOD123")
      (libsource (lib "eagle-import") (part "DIODE-SOD123"))
    )
    (comp (ref "Z28")
      (value "DIODE-SOD123")
      (footprint "eagle-import:SOD123")
      (libsource (lib "eagle-import") (part "DIODE-SOD123"))
    )
    (comp (ref "Z29")
      (value "DIODE-SOD123")
      (footprint "eagle-import:SOD123")
      (libsource (lib "eagle-import") (part "DIODE-SOD123"))
    )
    (comp (ref "Z30")
      (value "DIODE-SOD123")
      (footprint "eagle-import:SOD123")
      (libsource (lib "eagle-import") (part "DIODE-SOD123"))
    )
    (comp (ref "Z31")
      (value "DIODE-SOD123")
      (footprint "eagle-import:SOD123")
      (libsource (lib "eagle-import") (part "DIODE-SOD123"))
    )
    (comp (ref "Z32")
      (value "DIODE-SOD123")
      (footprint "eagle-import:SOD123")
      (libsource (lib "eagle-import") (part "DIODE-SOD123"))
    )
  )
  (nets
    (net (code "1") (name "/COMM") (class "Default")
      (node (ref "HEADER-22P1") (pin "20") (pinfunction "20_20") (pintype "bidirectional"))
      (node (ref "OPTO1") (pin "2") (pinfunction "C_2") (pintype "passive"))
      (node (ref "OPTO10") (pin "2") (pinfunction "C_2") (pintype "passive"))
      (node (ref "OPTO11") (pin "2") (pinfunction "C_2") (pintype "passive"))
      (node (ref "OPTO12") (pin "2") (pinfunction "C_2") (pintype "passive"))
      (node (ref "OPTO13") (pin "2") (pinfunction "C_2") (pintype "passive"))
      (node (ref "OPTO14") (pin "2") (pinfunction "C_2") (pintype "passive"))
      (node (ref "OPTO15") (pin "2") (pinfunction "C_2") (pintype "passive"))
      (node (ref "OPTO16") (pin "2") (pinfunction "C_2") (pintype "passive"))
      (node (ref "OPTO17") (pin "2") (pinfunction "C_2") (pintype "passive"))
      (node (ref "OPTO18") (pin "2") (pinfunction "C_2") (pintype "passive"))
      (node (ref "OPTO19") (pin "2") (pinfunction "C_2") (pintype "passive"))
      (node (ref "OPTO2") (pin "2") (pinfunction "C_2") (pintype "passive"))
      (node (ref "OPTO20") (pin "2") (pinfunction "C_2") (pintype "passive"))
      (node (ref "OPTO21") (pin "2") (pinfunction "C_2") (pintype "passive"))
      (node (ref "OPTO22") (pin "2") (pinfunction "C_2") (pintype "passive"))
      (node (ref "OPTO23") (pin "2") (pinfunction "C_2") (pintype "passive"))
      (node (ref "OPTO24") (pin "2") (pinfunction "C_2") (pintype "passive"))
      (node (ref "OPTO25") (pin "2") (pinfunction "C_2") (pintype "passive"))
      (node (ref "OPTO26") (pin "2") (pinfunction "C_2") (pintype "passive"))
      (node (ref "OPTO27") (pin "2") (pinfunction "C_2") (pintype "passive"))
      (node (ref "OPTO28") (pin "2") (pinfunction "C_2") (pintype "passive"))
      (node (ref "OPTO29") (pin "2") (pinfunction "C_2") (pintype "passive"))
      (node (ref "OPTO3") (pin "2") (pinfunction "C_2") (pintype "passive"))
      (node (ref "OPTO30") (pin "2") (pinfunction "C_2") (pintype "passive"))
      (node (ref "OPTO31") (pin "2") (pinfunction "C_2") (pintype "passive"))
      (node (ref "OPTO32") (pin "2") (pinfunction "C_2") (pintype "passive"))
      (node (ref "OPTO4") (pin "2") (pinfunction "C_2") (pintype "passive"))
      (node (ref "OPTO5") (pin "2") (pinfunction "C_2") (pintype "passive"))
      (node (ref "OPTO6") (pin "2") (pinfunction "C_2") (pintype "passive"))
      (node (ref "OPTO7") (pin "2") (pinfunction "C_2") (pintype "passive"))
      (node (ref "OPTO8") (pin "2") (pinfunction "C_2") (pintype "passive"))
      (node (ref "OPTO9") (pin "2") (pinfunction "C_2") (pintype "passive"))
      (node (ref "Z1") (pin "A") (pinfunction "A_A") (pintype "passive"))
      (node (ref "Z10") (pin "A") (pinfunction "A_A") (pintype "passive"))
      (node (ref "Z11") (pin "A") (pinfunction "A_A") (pintype "passive"))
      (node (ref "Z12") (pin "A") (pinfunction "A_A") (pintype "passive"))
      (node (ref "Z13") (pin "A") (pinfunction "A_A") (pintype "passive"))
      (node (ref "Z14") (pin "A") (pinfunction "A_A") (pintype "passive"))
      (node (ref "Z15") (pin "A") (pinfunction "A_A") (pintype "passive"))
      (node (ref "Z16") (pin "A") (pinfunction "A_A") (pintype "passive"))
      (node (ref "Z17") (pin "A") (pinfunction "A_A") (pintype "passive"))
      (node (ref "Z18") (pin "A") (pinfunction "A_A") (pintype "passive"))
      (node (ref "Z19") (pin "A") (pinfunction "A_A") (pintype "passive"))
      (node (ref "Z2") (pin "A") (pinfunction "A_A") (pintype "passive"))
      (node (ref "Z20") (pin "A") (pinfunction "A_A") (pintype "passive"))
      (node (ref "Z21") (pin "A") (pinfunction "A_A") (pintype "passive"))
      (node (ref "Z22") (pin "A") (pinfunction "A_A") (pintype "passive"))
      (node (ref "Z23") (pin "A") (pinfunction "A_A") (pintype "passive"))
      (node (ref "Z24") (pin "A") (pinfunction "A_A") (pintype "passive"))
      (node (ref "Z25") (pin "A") (pinfunction "A_A") (pintype "passive"))
      (node (ref "Z26") (pin "A") (pinfunction "A_A") (pintype "passive"))
      (node (ref "Z27") (pin "A") (pinfunction "A_A") (pintype "passive"))
      (node (ref "Z28") (pin "A") (pinfunction "A_A") (pintype "passive"))
      (node (ref "Z29") (pin "A") (pinfunction "A_A") (pintype "passive"))
      (node (ref "Z3") (pin "A") (pinfunction "A_A") (pintype "passive"))
      (node (ref "Z30") (pin "A") (pinfunction "A_A") (pintype "passive"))
      (node (ref "Z31") (pin "A") (pinfunction "A_A") (pintype "passive"))
      (node (ref "Z32") (pin "A") (pinfunction "A_A") (pintype "passive"))
      (node (ref "Z4") (pin "A") (pinfunction "A_A") (pintype "passive"))
      (node (ref "Z5") (pin "A") (pinfunction "A_A") (pintype "passive"))
      (node (ref "Z6") (pin "A") (pinfunction "A_A") (pintype "passive"))
      (node (ref "Z7") (pin "A") (pinfunction "A_A") (pintype "passive"))
      (node (ref "Z8") (pin "A") (pinfunction "A_A") (pintype "passive"))
      (node (ref "Z9") (pin "A") (pinfunction "A_A") (pintype "passive"))
    )
    (net (code "2") (name "/OUT1") (class "Default")
      (node (ref "IC4") (pin "21") (pinfunction "GPA0_21") (pintype "bidirectional"))
      (node (ref "OPTO1") (pin "4") (pinfunction "CT_4") (pintype "passive"))
      (node (ref "R49") (pin "1") (pinfunction "1_1") (pintype "passive"))
    )
    (net (code "3") (name "/OUT2") (class "Default")
      (node (ref "IC4") (pin "22") (pinfunction "GPA1_22") (pintype "bidirectional"))
      (node (ref "OPTO2") (pin "4") (pinfunction "CT_4") (pintype "passive"))
      (node (ref "R50") (pin "1") (pinfunction "1_1") (pintype "passive"))
    )
    (net (code "4") (name "/OUT3") (class "Default")
      (node (ref "IC4") (pin "23") (pinfunction "GPA2_23") (pintype "bidirectional"))
      (node (ref "OPTO3") (pin "4") (pinfunction "CT_4") (pintype "passive"))
      (node (ref "R51") (pin "1") (pinfunction "1_1") (pintype "passive"))
    )
    (net (code "5") (name "/OUT4") (class "Default")
      (node (ref "IC4") (pin "24") (pinfunction "GPA3_24") (pintype "bidirectional"))
      (node (ref "OPTO4") (pin "4") (pinfunction "CT_4") (pintype "passive"))
      (node (ref "R52") (pin "1") (pinfunction "1_1") (pintype "passive"))
    )
    (net (code "6") (name "/OUT5") (class "Default")
      (node (ref "IC4") (pin "25") (pinfunction "GPA4_25") (pintype "bidirectional"))
      (node (ref "OPTO5") (pin "4") (pinfunction "CT_4") (pintype "passive"))
      (node (ref "R53") (pin "1") (pinfunction "1_1") (pintype "passive"))
    )
    (net (code "7") (name "/OUT6") (class "Default")
      (node (ref "IC4") (pin "26") (pinfunction "GPA5_26") (pintype "bidirectional"))
      (node (ref "OPTO6") (pin "4") (pinfunction "CT_4") (pintype "passive"))
      (node (ref "R54") (pin "1") (pinfunction "1_1") (pintype "passive"))
    )
    (net (code "8") (name "/OUT7") (class "Default")
      (node (ref "IC4") (pin "27") (pinfunction "GPA6_27") (pintype "bidirectional"))
      (node (ref "OPTO7") (pin "4") (pinfunction "CT_4") (pintype "passive"))
      (node (ref "R55") (pin "1") (pinfunction "1_1") (pintype "passive"))
    )
    (net (code "9") (name "/OUT8") (class "Default")
      (node (ref "IC4") (pin "28") (pinfunction "GPA7_28") (pintype "bidirectional"))
      (node (ref "OPTO8") (pin "4") (pinfunction "CT_4") (pintype "passive"))
      (node (ref "R56") (pin "1") (pinfunction "1_1") (pintype "passive"))
    )
    (net (code "10") (name "/OUT9") (class "Default")
      (node (ref "IC4") (pin "1") (pinfunction "GPB0_1") (pintype "bidirectional"))
      (node (ref "OPTO9") (pin "4") (pinfunction "CT_4") (pintype "passive"))
      (node (ref "R57") (pin "1") (pinfunction "1_1") (pintype "passive"))
    )
    (net (code "11") (name "/OUT10") (class "Default")
      (node (ref "IC4") (pin "2") (pinfunction "GPB1_2") (pintype "bidirectional"))
      (node (ref "OPTO10") (pin "4") (pinfunction "CT_4") (pintype "passive"))
      (node (ref "R58") (pin "1") (pinfunction "1_1") (pintype "passive"))
    )
    (net (code "12") (name "/OUT11") (class "Default")
      (node (ref "IC4") (pin "3") (pinfunction "GPB2_3") (pintype "bidirectional"))
      (node (ref "OPTO11") (pin "4") (pinfunction "CT_4") (pintype "passive"))
      (node (ref "R59") (pin "1") (pinfunction "1_1") (pintype "passive"))
    )
    (net (code "13") (name "/OUT12") (class "Default")
      (node (ref "IC4") (pin "4") (pinfunction "GPB3_4") (pintype "bidirectional"))
      (node (ref "OPTO12") (pin "4") (pinfunction "CT_4") (pintype "passive"))
      (node (ref "R60") (pin "1") (pinfunction "1_1") (pintype "passive"))
    )
    (net (code "14") (name "/OUT13") (class "Default")
      (node (ref "IC4") (pin "5") (pinfunction "GPB4_5") (pintype "bidirectional"))
      (node (ref "OPTO13") (pin "4") (pinfunction "CT_4") (pintype "passive"))
      (node (ref "R61") (pin "1") (pinfunction "1_1") (pintype "passive"))
    )
    (net (code "15") (name "/OUT14") (class "Default")
      (node (ref "IC4") (pin "6") (pinfunction "GPB5_6") (pintype "bidirectional"))
      (node (ref "OPTO14") (pin "4") (pinfunction "CT_4") (pintype "passive"))
      (node (ref "R62") (pin "1") (pinfunction "1_1") (pintype "passive"))
    )
    (net (code "16") (name "/OUT15") (class "Default")
      (node (ref "IC4") (pin "7") (pinfunction "GPB6_7") (pintype "bidirectional"))
      (node (ref "OPTO15") (pin "4") (pinfunction "CT_4") (pintype "passive"))
      (node (ref "R63") (pin "1") (pinfunction "1_1") (pintype "passive"))
    )
    (net (code "17") (name "/OUT16") (class "Default")
      (node (ref "IC4") (pin "8") (pinfunction "GPB7_8") (pintype "bidirectional"))
      (node (ref "OPTO16") (pin "4") (pinfunction "CT_4") (pintype "passive"))
      (node (ref "R64") (pin "1") (pinfunction "1_1") (pintype "passive"))
    )
    (net (code "18") (name "/OUT17") (class "Default")
      (node (ref "IC1") (pin "21") (pinfunction "GPA0_21") (pintype "bidirectional"))
      (node (ref "OPTO17") (pin "4") (pinfunction "CT_4") (pintype "passive"))
      (node (ref "R65") (pin "1") (pinfunction "1_1") (pintype "passive"))
    )
    (net (code "19") (name "/OUT18") (class "Default")
      (node (ref "IC1") (pin "22") (pinfunction "GPA1_22") (pintype "bidirectional"))
      (node (ref "OPTO18") (pin "4") (pinfunction "CT_4") (pintype "passive"))
      (node (ref "R66") (pin "1") (pinfunction "1_1") (pintype "passive"))
    )
    (net (code "20") (name "/OUT19") (class "Default")
      (node (ref "IC1") (pin "23") (pinfunction "GPA2_23") (pintype "bidirectional"))
      (node (ref "OPTO19") (pin "4") (pinfunction "CT_4") (pintype "passive"))
      (node (ref "R67") (pin "1") (pinfunction "1_1") (pintype "passive"))
    )
    (net (code "21") (name "/OUT20") (class "Default")
      (node (ref "IC1") (pin "24") (pinfunction "GPA3_24") (pintype "bidirectional"))
      (node (ref "OPTO20") (pin "4") (pinfunction "CT_4") (pintype "passive"))
      (node (ref "R68") (pin "1") (pinfunction "1_1") (pintype "passive"))
    )
    (net (code "22") (name "/OUT21") (class "Default")
      (node (ref "IC1") (pin "25") (pinfunction "GPA4_25") (pintype "bidirectional"))
      (node (ref "OPTO21") (pin "4") (pinfunction "CT_4") (pintype "passive"))
      (node (ref "R69") (pin "1") (pinfunction "1_1") (pintype "passive"))
    )
    (net (code "23") (name "/OUT22") (class "Default")
      (node (ref "IC1") (pin "26") (pinfunction "GPA5_26") (pintype "bidirectional"))
      (node (ref "OPTO22") (pin "4") (pinfunction "CT_4") (pintype "passive"))
      (node (ref "R70") (pin "1") (pinfunction "1_1") (pintype "passive"))
    )
    (net (code "24") (name "/OUT23") (class "Default")
      (node (ref "IC1") (pin "27") (pinfunction "GPA6_27") (pintype "bidirectional"))
      (node (ref "OPTO23") (pin "4") (pinfunction "CT_4") (pintype "passive"))
      (node (ref "R71") (pin "1") (pinfunction "1_1") (pintype "passive"))
    )
    (net (code "25") (name "/OUT24") (class "Default")
      (node (ref "IC1") (pin "28") (pinfunction "GPA7_28") (pintype "bidirectional"))
      (node (ref "OPTO24") (pin "4") (pinfunction "CT_4") (pintype "passive"))
      (node (ref "R72") (pin "1") (pinfunction "1_1") (pintype "passive"))
    )
    (net (code "26") (name "/OUT25") (class "Default")
      (node (ref "IC1") (pin "1") (pinfunction "GPB0_1") (pintype "bidirectional"))
      (node (ref "OPTO25") (pin "4") (pinfunction "CT_4") (pintype "passive"))
      (node (ref "R73") (pin "1") (pinfunction "1_1") (pintype "passive"))
    )
    (net (code "27") (name "/OUT26") (class "Default")
      (node (ref "IC1") (pin "2") (pinfunction "GPB1_2") (pintype "bidirectional"))
      (node (ref "OPTO26") (pin "4") (pinfunction "CT_4") (pintype "passive"))
      (node (ref "R74") (pin "1") (pinfunction "1_1") (pintype "passive"))
    )
    (net (code "28") (name "/OUT27") (class "Default")
      (node (ref "IC1") (pin "3") (pinfunction "GPB2_3") (pintype "bidirectional"))
      (node (ref "OPTO27") (pin "4") (pinfunction "CT_4") (pintype "passive"))
      (node (ref "R75") (pin "1") (pinfunction "1_1") (pintype "passive"))
    )
    (net (code "29") (name "/OUT28") (class "Default")
      (node (ref "IC1") (pin "4") (pinfunction "GPB3_4") (pintype "bidirectional"))
      (node (ref "OPTO28") (pin "4") (pinfunction "CT_4") (pintype "passive"))
      (node (ref "R76") (pin "1") (pinfunction "1_1") (pintype "passive"))
    )
    (net (code "30") (name "/OUT29") (class "Default")
      (node (ref "IC1") (pin "5") (pinfunction "GPB4_5") (pintype "bidirectional"))
      (node (ref "OPTO29") (pin "4") (pinfunction "CT_4") (pintype "passive"))
      (node (ref "R77") (pin "1") (pinfunction "1_1") (pintype "passive"))
    )
    (net (code "31") (name "/OUT30") (class "Default")
      (node (ref "IC1") (pin "6") (pinfunction "GPB5_6") (pintype "bidirectional"))
      (node (ref "OPTO30") (pin "4") (pinfunction "CT_4") (pintype "passive"))
      (node (ref "R78") (pin "1") (pinfunction "1_1") (pintype "passive"))
    )
    (net (code "32") (name "/OUT31") (class "Default")
      (node (ref "IC1") (pin "7") (pinfunction "GPB6_7") (pintype "bidirectional"))
      (node (ref "OPTO31") (pin "4") (pinfunction "CT_4") (pintype "passive"))
      (node (ref "R79") (pin "1") (pinfunction "1_1") (pintype "passive"))
    )
    (net (code "33") (name "/OUT32") (class "Default")
      (node (ref "IC1") (pin "8") (pinfunction "GPB7_8") (pintype "bidirectional"))
      (node (ref "OPTO32") (pin "4") (pinfunction "CT_4") (pintype "passive"))
      (node (ref "R80") (pin "1") (pinfunction "1_1") (pintype "passive"))
    )
    (net (code "34") (name "/P1") (class "Default")
      (node (ref "HEADER-29P1") (pin "1") (pinfunction "1_1") (pintype "bidirectional"))
      (node (ref "R1") (pin "1") (pinfunction "1_1") (pintype "passive"))
    )
    (net (code "35") (name "/P2") (class "Default")
      (node (ref "HEADER-29P1") (pin "2") (pinfunction "2_2") (pintype "bidirectional"))
      (node (ref "R2") (pin "1") (pinfunction "1_1") (pintype "passive"))
    )
    (net (code "36") (name "/P3") (class "Default")
      (node (ref "HEADER-29P1") (pin "3") (pinfunction "3_3") (pintype "bidirectional"))
      (node (ref "R3") (pin "1") (pinfunction "1_1") (pintype "passive"))
    )
    (net (code "37") (name "/P4") (class "Default")
      (node (ref "HEADER-29P1") (pin "4") (pinfunction "4_4") (pintype "bidirectional"))
      (node (ref "R4") (pin "1") (pinfunction "1_1") (pintype "passive"))
    )
    (net (code "38") (name "/P5") (class "Default")
      (node (ref "HEADER-29P1") (pin "5") (pinfunction "5_5") (pintype "bidirectional"))
      (node (ref "R5") (pin "1") (pinfunction "1_1") (pintype "passive"))
    )
    (net (code "39") (name "/P6") (class "Default")
      (node (ref "HEADER-29P1") (pin "6") (pinfunction "6_6") (pintype "bidirectional"))
      (node (ref "R6") (pin "1") (pinfunction "1_1") (pintype "passive"))
    )
    (net (code "40") (name "/P7") (class "Default")
      (node (ref "HEADER-29P1") (pin "7") (pinfunction "7_7") (pintype "bidirectional"))
      (node (ref "R7") (pin "1") (pinfunction "1_1") (pintype "passive"))
    )
    (net (code "41") (name "/P8") (class "Default")
      (node (ref "HEADER-29P1") (pin "8") (pinfunction "8_8") (pintype "bidirectional"))
      (node (ref "R8") (pin "1") (pinfunction "1_1") (pintype "passive"))
    )
    (net (code "42") (name "/P9") (class "Default")
      (node (ref "HEADER-29P1") (pin "9") (pinfunction "9_9") (pintype "bidirectional"))
      (node (ref "R9") (pin "1") (pinfunction "1_1") (pintype "passive"))
    )
    (net (code "43") (name "/P10") (class "Default")
      (node (ref "HEADER-29P1") (pin "10") (pinfunction "10_10") (pintype "bidirectional"))
      (node (ref "R10") (pin "1") (pinfunction "1_1") (pintype "passive"))
    )
    (net (code "44") (name "/P11") (class "Default")
      (node (ref "HEADER-29P1") (pin "11") (pinfunction "11_11") (pintype "bidirectional"))
      (node (ref "R11") (pin "1") (pinfunction "1_1") (pintype "passive"))
    )
    (net (code "45") (name "/P12") (class "Default")
      (node (ref "HEADER-29P1") (pin "12") (pinfunction "12_12") (pintype "bidirectional"))
      (node (ref "R12") (pin "1") (pinfunction "1_1") (pintype "passive"))
    )
    (net (code "46") (name "/P13") (class "Default")
      (node (ref "HEADER-29P1") (pin "13") (pinfunction "13_13") (pintype "bidirectional"))
      (node (ref "R13") (pin "1") (pinfunction "1_1") (pintype "passive"))
    )
    (net (code "47") (name "/P14") (class "Default")
      (node (ref "HEADER-29P1") (pin "14") (pinfunction "14_14") (pintype "bidirectional"))
      (node (ref "R14") (pin "1") (pinfunction "1_1") (pintype "passive"))
    )
    (net (code "48") (name "/P15") (class "Default")
      (node (ref "HEADER-29P1") (pin "15") (pinfunction "15_15") (pintype "bidirectional"))
      (node (ref "R15") (pin "1") (pinfunction "1_1") (pintype "passive"))
    )
    (net (code "49") (name "/P16") (class "Default")
      (node (ref "HEADER-29P1") (pin "16") (pinfunction "16_16") (pintype "bidirectional"))
      (node (ref "R16") (pin "1") (pinfunction "1_1") (pintype "passive"))
    )
    (net (code "50") (name "/P17") (class "Default")
      (node (ref "HEADER-29P1") (pin "17") (pinfunction "17_17") (pintype "bidirectional"))
      (node (ref "R17") (pin "1") (pinfunction "1_1") (pintype "passive"))
    )
    (net (code "51") (name "/P18") (class "Default")
      (node (ref "HEADER-29P1") (pin "18") (pinfunction "18_18") (pintype "bidirectional"))
      (node (ref "R18") (pin "1") (pinfunction "1_1") (pintype "passive"))
    )
    (net (code "52") (name "/P19") (class "Default")
      (node (ref "HEADER-29P1") (pin "19") (pinfunction "19_19") (pintype "bidirectional"))
      (node (ref "R19") (pin "1") (pinfunction "1_1") (pintype "passive"))
    )
    (net (code "53") (name "/P20") (class "Default")
      (node (ref "HEADER-29P1") (pin "20") (pinfunction "20_20") (pintype "bidirectional"))
      (node (ref "R20") (pin "1") (pinfunction "1_1") (pintype "passive"))
    )
    (net (code "54") (name "/P21") (class "Default")
      (node (ref "HEADER-29P1") (pin "21") (pinfunction "21_21") (pintype "bidirectional"))
      (node (ref "R21") (pin "1") (pinfunction "1_1") (pintype "passive"))
    )
    (net (code "55") (name "/P22") (class "Default")
      (node (ref "HEADER-29P1") (pin "22") (pinfunction "22_22") (pintype "bidirectional"))
      (node (ref "R22") (pin "1") (pinfunction "1_1") (pintype "passive"))
    )
    (net (code "56") (name "/P23") (class "Default")
      (node (ref "HEADER-29P1") (pin "23") (pinfunction "23_23") (pintype "bidirectional"))
      (node (ref "R23") (pin "1") (pinfunction "1_1") (pintype "passive"))
    )
    (net (code "57") (name "/P24") (class "Default")
      (node (ref "HEADER-29P1") (pin "24") (pinfunction "24_24") (pintype "bidirectional"))
      (node (ref "R24") (pin "1") (pinfunction "1_1") (pintype "passive"))
    )
    (net (code "58") (name "/P25") (class "Default")
      (node (ref "HEADER-29P1") (pin "25") (pinfunction "25_25") (pintype "bidirectional"))
      (node (ref "R25") (pin "1") (pinfunction "1_1") (pintype "passive"))
    )
    (net (code "59") (name "/P26") (class "Default")
      (node (ref "HEADER-29P1") (pin "26") (pinfunction "26_26") (pintype "bidirectional"))
      (node (ref "R26") (pin "1") (pinfunction "1_1") (pintype "passive"))
    )
    (net (code "60") (name "/P27") (class "Default")
      (node (ref "HEADER-29P1") (pin "27") (pinfunction "27_27") (pintype "bidirectional"))
      (node (ref "R27") (pin "1") (pinfunction "1_1") (pintype "passive"))
    )
    (net (code "61") (name "/P28") (class "Default")
      (node (ref "HEADER-29P1") (pin "28") (pinfunction "28_28") (pintype "bidirectional"))
      (node (ref "R28") (pin "1") (pinfunction "1_1") (pintype "passive"))
    )
    (net (code "62") (name "/P29") (class "Default")
      (node (ref "HEADER-29P1") (pin "29") (pinfunction "29_29") (pintype "bidirectional"))
      (node (ref "R29") (pin "1") (pinfunction "1_1") (pintype "passive"))
    )
    (net (code "63") (name "/P30") (class "Default")
      (node (ref "HEADER-22P1") (pin "1") (pinfunction "1_1") (pintype "bidirectional"))
      (node (ref "R30") (pin "1") (pinfunction "1_1") (pintype "passive"))
    )
    (net (code "64") (name "/P31") (class "Default")
      (node (ref "HEADER-22P1") (pin "2") (pinfunction "2_2") (pintype "bidirectional"))
      (node (ref "R31") (pin "1") (pinfunction "1_1") (pintype "passive"))
    )
    (net (code "65") (name "/P32") (class "Default")
      (node (ref "HEADER-22P1") (pin "3") (pinfunction "3_3") (pintype "bidirectional"))
      (node (ref "R32") (pin "1") (pinfunction "1_1") (pintype "passive"))
    )
    (net (code "66") (name "24V+") (class "Default")
      (node (ref "HEADER-22P1") (pin "22") (pinfunction "22_22") (pintype "bidirectional"))
      (node (ref "JP1") (pin "P$1") (pinfunction "1_P$1") (pintype "passive"))
      (node (ref "K2") (pin "S1") (pinfunction "S_S1") (pintype "passive"))
      (node (ref "K3") (pin "S1") (pinfunction "S_S1") (pintype "passive"))
      (node (ref "K4") (pin "S1") (pinfunction "S_S1") (pintype "passive"))
      (node (ref "K5") (pin "S1") (pinfunction "S_S1") (pintype "passive"))
      (node (ref "K6") (pin "S1") (pinfunction "S_S1") (pintype "passive"))
      (node (ref "K7") (pin "S1") (pinfunction "S_S1") (pintype "passive"))
      (node (ref "K8") (pin "S1") (pinfunction "S_S1") (pintype "passive"))
      (node (ref "K9") (pin "S1") (pinfunction "S_S1") (pintype "passive"))
    )
    (net (code "67") (name "A+") (class "Default")
      (node (ref "JP2") (pin "7") (pinfunction "7_7") (pintype "passive"))
      (node (ref "TTL-RS1") (pin "A") (pinfunction "A_A") (pintype "bidirectional"))
    )
    (net (code "68") (name "B-") (class "Default")
      (node (ref "JP2") (pin "5") (pinfunction "5_5") (pintype "passive"))
      (node (ref "TTL-RS1") (pin "B") (pinfunction "B_B") (pintype "bidirectional"))
    )
    (net (code "69") (name "DO1") (class "Default")
      (node (ref "JP5") (pin "1") (pinfunction "1_1") (pintype "passive"))
      (node (ref "R34") (pin "2") (pinfunction "2_2") (pintype "passive"))
    )
    (net (code "70") (name "DO2") (class "Default")
      (node (ref "JP5") (pin "2") (pinfunction "2_2") (pintype "passive"))
      (node (ref "R36") (pin "2") (pinfunction "2_2") (pintype "passive"))
    )
    (net (code "71") (name "DO3") (class "Default")
      (node (ref "JP5") (pin "3") (pinfunction "3_3") (pintype "passive"))
      (node (ref "R38") (pin "2") (pinfunction "2_2") (pintype "passive"))
    )
    (net (code "72") (name "DO4") (class "Default")
      (node (ref "JP5") (pin "4") (pinfunction "4_4") (pintype "passive"))
      (node (ref "R40") (pin "2") (pinfunction "2_2") (pintype "passive"))
    )
    (net (code "73") (name "DO5") (class "Default")
      (node (ref "JP5") (pin "5") (pinfunction "5_5") (pintype "passive"))
      (node (ref "R42") (pin "2") (pinfunction "2_2") (pintype "passive"))
    )
    (net (code "74") (name "DO6") (class "Default")
      (node (ref "JP5") (pin "6") (pinfunction "6_6") (pintype "passive"))
      (node (ref "R44") (pin "2") (pinfunction "2_2") (pintype "passive"))
    )
    (net (code "75") (name "DO7") (class "Default")
      (node (ref "JP5") (pin "7") (pinfunction "7_7") (pintype "passive"))
      (node (ref "R46") (pin "2") (pinfunction "2_2") (pintype "passive"))
    )
    (net (code "76") (name "DO8") (class "Default")
      (node (ref "JP5") (pin "8") (pinfunction "8_8") (pintype "passive"))
      (node (ref "R48") (pin "2") (pinfunction "2_2") (pintype "passive"))
    )
    (net (code "77") (name "GND") (class "Default")
      (node (ref "IC1") (pin "10") (pinfunction "VSS_10") (pintype "power_in"))
      (node (ref "IC4") (pin "10") (pinfunction "VSS_10") (pintype "power_in"))
      (node (ref "JP2") (pin "2") (pinfunction "2_2") (pintype "passive"))
      (node (ref "JP4") (pin "2") (pinfunction "2_2") (pintype "passive"))
      (node (ref "JP4") (pin "4") (pinfunction "4_4") (pintype "passive"))
      (node (ref "OPTO1") (pin "3") (pinfunction "ET_3") (pintype "passive"))
      (node (ref "OPTO10") (pin "3") (pinfunction "ET_3") (pintype "passive"))
      (node (ref "OPTO11") (pin "3") (pinfunction "ET_3") (pintype "passive"))
      (node (ref "OPTO12") (pin "3") (pinfunction "ET_3") (pintype "passive"))
      (node (ref "OPTO13") (pin "3") (pinfunction "ET_3") (pintype "passive"))
      (node (ref "OPTO14") (pin "3") (pinfunction "ET_3") (pintype "passive"))
      (node (ref "OPTO15") (pin "3") (pinfunction "ET_3") (pintype "passive"))
      (node (ref "OPTO16") (pin "3") (pinfunction "ET_3") (pintype "passive"))
      (node (ref "OPTO17") (pin "3") (pinfunction "ET_3") (pintype "passive"))
      (node (ref "OPTO18") (pin "3") (pinfunction "ET_3") (pintype "passive"))
      (node (ref "OPTO19") (pin "3") (pinfunction "ET_3") (pintype "passive"))
      (node (ref "OPTO2") (pin "3") (pinfunction "ET_3") (pintype "passive"))
      (node (ref "OPTO20") (pin "3") (pinfunction "ET_3") (pintype "passive"))
      (node (ref "OPTO21") (pin "3") (pinfunction "ET_3") (pintype "passive"))
      (node (ref "OPTO22") (pin "3") (pinfunction "ET_3") (pintype "passive"))
      (node (ref "OPTO23") (pin "3") (pinfunction "ET_3") (pintype "passive"))
      (node (ref "OPTO24") (pin "3") (pinfunction "ET_3") (pintype "passive"))
      (node (ref "OPTO25") (pin "3") (pinfunction "ET_3") (pintype "passive"))
      (node (ref "OPTO26") (pin "3") (pinfunction "ET_3") (pintype "passive"))
      (node (ref "OPTO27") (pin "3") (pinfunction "ET_3") (pintype "passive"))
      (node (ref "OPTO28") (pin "3") (pinfunction "ET_3") (pintype "passive"))
      (node (ref "OPTO29") (pin "3") (pinfunction "ET_3") (pintype "passive"))
      (node (ref "OPTO3") (pin "3") (pinfunction "ET_3") (pintype "passive"))
      (node (ref "OPTO30") (pin "3") (pinfunction "ET_3") (pintype "passive"))
      (node (ref "OPTO31") (pin "3") (pinfunction "ET_3") (pintype "passive"))
      (node (ref "OPTO32") (pin "3") (pinfunction "ET_3") (pintype "passive"))
      (node (ref "OPTO4") (pin "3") (pinfunction "ET_3") (pintype "passive"))
      (node (ref "OPTO5") (pin "3") (pinfunction "ET_3") (pintype "passive"))
      (node (ref "OPTO6") (pin "3") (pinfunction "ET_3") (pintype "passive"))
      (node (ref "OPTO7") (pin "3") (pinfunction "ET_3") (pintype "passive"))
      (node (ref "OPTO8") (pin "3") (pinfunction "ET_3") (pintype "passive"))
      (node (ref "OPTO9") (pin "3") (pinfunction "ET_3") (pintype "passive"))
      (node (ref "Q2") (pin "2") (pinfunction "E_2") (pintype "passive"))
      (node (ref "Q3") (pin "2") (pinfunction "E_2") (pintype "passive"))
      (node (ref "Q4") (pin "2") (pinfunction "E_2") (pintype "passive"))
      (node (ref "Q5") (pin "2") (pinfunction "E_2") (pintype "passive"))
      (node (ref "Q6") (pin "2") (pinfunction "E_2") (pintype "passive"))
      (node (ref "Q7") (pin "2") (pinfunction "E_2") (pintype "passive"))
      (node (ref "Q8") (pin "2") (pinfunction "E_2") (pintype "passive"))
      (node (ref "Q9") (pin "2") (pinfunction "E_2") (pintype "passive"))
      (node (ref "R104") (pin "1") (pinfunction "1_1") (pintype "passive"))
      (node (ref "R105") (pin "1") (pinfunction "1_1") (pintype "passive"))
      (node (ref "R106") (pin "1") (pinfunction "1_1") (pintype "passive"))
      (node (ref "R109") (pin "1") (pinfunction "1_1") (pintype "passive"))
      (node (ref "R110") (pin "1") (pinfunction "1_1") (pintype "passive"))
      (node (ref "TTL-RS1") (pin "GND") (pinfunction "GND_GND") (pintype "bidirectional"))
      (node (ref "U1") (pin "2") (pinfunction "C_2") (pintype "passive"))
      (node (ref "U2") (pin "2") (pinfunction "C_2") (pintype "passive"))
      (node (ref "U3") (pin "2") (pinfunction "C_2") (pintype "passive"))
      (node (ref "U4") (pin "2") (pinfunction "C_2") (pintype "passive"))
      (node (ref "U5") (pin "2") (pinfunction "C_2") (pintype "passive"))
      (node (ref "U6") (pin "2") (pinfunction "C_2") (pintype "passive"))
      (node (ref "U7") (pin "2") (pinfunction "C_2") (pintype "passive"))
      (node (ref "U8") (pin "2") (pinfunction "C_2") (pintype "passive"))
      (node (ref "USB2RS1") (pin "4") (pinfunction "4_4") (pintype "bidirectional"))
    )
    (net (code "78") (name "Net-(D2-K)") (class "Default")
      (node (ref "D2") (pin "C") (pinfunction "K_C") (pintype "passive"))
      (node (ref "LED1") (pin "+") (pinfunction "+_+") (pintype "passive"))
    )
    (net (code "79") (name "Net-(D2-PadA)") (class "Default")
      (node (ref "D2") (pin "A") (pinfunction "A_A") (pintype "passive"))
      (node (ref "R1") (pin "2") (pinfunction "2_2") (pintype "passive"))
    )
    (net (code "80") (name "Net-(D3-K)") (class "Default")
      (node (ref "D3") (pin "C") (pinfunction "K_C") (pintype "passive"))
      (node (ref "LED2") (pin "+") (pinfunction "+_+") (pintype "passive"))
    )
    (net (code "81") (name "Net-(D3-PadA)") (class "Default")
      (node (ref "D3") (pin "A") (pinfunction "A_A") (pintype "passive"))
      (node (ref "R2") (pin "2") (pinfunction "2_2") (pintype "passive"))
    )
    (net (code "82") (name "Net-(D4-K)") (class "Default")
      (node (ref "D4") (pin "C") (pinfunction "K_C") (pintype "passive"))
      (node (ref "LED3") (pin "+") (pinfunction "+_+") (pintype "passive"))
    )
    (net (code "83") (name "Net-(D4-PadA)") (class "Default")
      (node (ref "D4") (pin "A") (pinfunction "A_A") (pintype "passive"))
      (node (ref "R3") (pin "2") (pinfunction "2_2") (pintype "passive"))
    )
    (net (code "84") (name "Net-(D5-K)") (class "Default")
      (node (ref "D5") (pin "C") (pinfunction "K_C") (pintype "passive"))
      (node (ref "LED4") (pin "+") (pinfunction "+_+") (pintype "passive"))
    )
    (net (code "85") (name "Net-(D5-PadA)") (class "Default")
      (node (ref "D5") (pin "A") (pinfunction "A_A") (pintype "passive"))
      (node (ref "R4") (pin "2") (pinfunction "2_2") (pintype "passive"))
    )
    (net (code "86") (name "Net-(D6-K)") (class "Default")
      (node (ref "D6") (pin "C") (pinfunction "K_C") (pintype "passive"))
      (node (ref "LED5") (pin "+") (pinfunction "+_+") (pintype "passive"))
    )
    (net (code "87") (name "Net-(D6-PadA)") (class "Default")
      (node (ref "D6") (pin "A") (pinfunction "A_A") (pintype "passive"))
      (node (ref "R5") (pin "2") (pinfunction "2_2") (pintype "passive"))
    )
    (net (code "88") (name "Net-(D7-K)") (class "Default")
      (node (ref "D7") (pin "C") (pinfunction "K_C") (pintype "passive"))
      (node (ref "LED6") (pin "+") (pinfunction "+_+") (pintype "passive"))
    )
    (net (code "89") (name "Net-(D7-PadA)") (class "Default")
      (node (ref "D7") (pin "A") (pinfunction "A_A") (pintype "passive"))
      (node (ref "R6") (pin "2") (pinfunction "2_2") (pintype "passive"))
    )
    (net (code "90") (name "Net-(D8-K)") (class "Default")
      (node (ref "D8") (pin "C") (pinfunction "K_C") (pintype "passive"))
      (node (ref "LED7") (pin "+") (pinfunction "+_+") (pintype "passive"))
    )
    (net (code "91") (name "Net-(D8-PadA)") (class "Default")
      (node (ref "D8") (pin "A") (pinfunction "A_A") (pintype "passive"))
      (node (ref "R7") (pin "2") (pinfunction "2_2") (pintype "passive"))
    )
    (net (code "92") (name "Net-(D9-K)") (class "Default")
      (node (ref "D9") (pin "C") (pinfunction "K_C") (pintype "passive"))
      (node (ref "LED8") (pin "+") (pinfunction "+_+") (pintype "passive"))
    )
    (net (code "93") (name "Net-(D9-PadA)") (class "Default")
      (node (ref "D9") (pin "A") (pinfunction "A_A") (pintype "passive"))
      (node (ref "R8") (pin "2") (pinfunction "2_2") (pintype "passive"))
    )
    (net (code "94") (name "Net-(D10-K)") (class "Default")
      (node (ref "D10") (pin "C") (pinfunction "K_C") (pintype "passive"))
      (node (ref "LED9") (pin "+") (pinfunction "+_+") (pintype "passive"))
    )
    (net (code "95") (name "Net-(D10-PadA)") (class "Default")
      (node (ref "D10") (pin "A") (pinfunction "A_A") (pintype "passive"))
      (node (ref "R9") (pin "2") (pinfunction "2_2") (pintype "passive"))
    )
    (net (code "96") (name "Net-(D11-K)") (class "Default")
      (node (ref "D11") (pin "C") (pinfunction "K_C") (pintype "passive"))
      (node (ref "LED10") (pin "+") (pinfunction "+_+") (pintype "passive"))
    )
    (net (code "97") (name "Net-(D11-PadA)") (class "Default")
      (node (ref "D11") (pin "A") (pinfunction "A_A") (pintype "passive"))
      (node (ref "R10") (pin "2") (pinfunction "2_2") (pintype "passive"))
    )
    (net (code "98") (name "Net-(D12-K)") (class "Default")
      (node (ref "D12") (pin "C") (pinfunction "K_C") (pintype "passive"))
      (node (ref "LED11") (pin "+") (pinfunction "+_+") (pintype "passive"))
    )
    (net (code "99") (name "Net-(D12-PadA)") (class "Default")
      (node (ref "D12") (pin "A") (pinfunction "A_A") (pintype "passive"))
      (node (ref "R11") (pin "2") (pinfunction "2_2") (pintype "passive"))
    )
    (net (code "100") (name "Net-(D13-K)") (class "Default")
      (node (ref "D13") (pin "C") (pinfunction "K_C") (pintype "passive"))
      (node (ref "LED12") (pin "+") (pinfunction "+_+") (pintype "passive"))
    )
    (net (code "101") (name "Net-(D13-PadA)") (class "Default")
      (node (ref "D13") (pin "A") (pinfunction "A_A") (pintype "passive"))
      (node (ref "R12") (pin "2") (pinfunction "2_2") (pintype "passive"))
    )
    (net (code "102") (name "Net-(D14-K)") (class "Default")
      (node (ref "D14") (pin "C") (pinfunction "K_C") (pintype "passive"))
      (node (ref "LED13") (pin "+") (pinfunction "+_+") (pintype "passive"))
    )
    (net (code "103") (name "Net-(D14-PadA)") (class "Default")
      (node (ref "D14") (pin "A") (pinfunction "A_A") (pintype "passive"))
      (node (ref "R13") (pin "2") (pinfunction "2_2") (pintype "passive"))
    )
    (net (code "104") (name "Net-(D15-K)") (class "Default")
      (node (ref "D15") (pin "C") (pinfunction "K_C") (pintype "passive"))
      (node (ref "LED14") (pin "+") (pinfunction "+_+") (pintype "passive"))
    )
    (net (code "105") (name "Net-(D15-PadA)") (class "Default")
      (node (ref "D15") (pin "A") (pinfunction "A_A") (pintype "passive"))
      (node (ref "R14") (pin "2") (pinfunction "2_2") (pintype "passive"))
    )
    (net (code "106") (name "Net-(D16-K)") (class "Default")
      (node (ref "D16") (pin "C") (pinfunction "K_C") (pintype "passive"))
      (node (ref "LED15") (pin "+") (pinfunction "+_+") (pintype "passive"))
    )
    (net (code "107") (name "Net-(D16-PadA)") (class "Default")
      (node (ref "D16") (pin "A") (pinfunction "A_A") (pintype "passive"))
      (node (ref "R15") (pin "2") (pinfunction "2_2") (pintype "passive"))
    )
    (net (code "108") (name "Net-(D17-K)") (class "Default")
      (node (ref "D17") (pin "C") (pinfunction "K_C") (pintype "passive"))
      (node (ref "LED16") (pin "+") (pinfunction "+_+") (pintype "passive"))
    )
    (net (code "109") (name "Net-(D17-PadA)") (class "Default")
      (node (ref "D17") (pin "A") (pinfunction "A_A") (pintype "passive"))
      (node (ref "R16") (pin "2") (pinfunction "2_2") (pintype "passive"))
    )
    (net (code "110") (name "Net-(D18-K)") (class "Default")
      (node (ref "D18") (pin "C") (pinfunction "K_C") (pintype "passive"))
      (node (ref "LED17") (pin "+") (pinfunction "+_+") (pintype "passive"))
    )
    (net (code "111") (name "Net-(D18-PadA)") (class "Default")
      (node (ref "D18") (pin "A") (pinfunction "A_A") (pintype "passive"))
      (node (ref "R17") (pin "2") (pinfunction "2_2") (pintype "passive"))
    )
    (net (code "112") (name "Net-(D19-K)") (class "Default")
      (node (ref "D19") (pin "C") (pinfunction "K_C") (pintype "passive"))
      (node (ref "LED18") (pin "+") (pinfunction "+_+") (pintype "passive"))
    )
    (net (code "113") (name "Net-(D19-PadA)") (class "Default")
      (node (ref "D19") (pin "A") (pinfunction "A_A") (pintype "passive"))
      (node (ref "R18") (pin "2") (pinfunction "2_2") (pintype "passive"))
    )
    (net (code "114") (name "Net-(D20-K)") (class "Default")
      (node (ref "D20") (pin "C") (pinfunction "K_C") (pintype "passive"))
      (node (ref "LED19") (pin "+") (pinfunction "+_+") (pintype "passive"))
    )
    (net (code "115") (name "Net-(D20-PadA)") (class "Default")
      (node (ref "D20") (pin "A") (pinfunction "A_A") (pintype "passive"))
      (node (ref "R19") (pin "2") (pinfunction "2_2") (pintype "passive"))
    )
    (net (code "116") (name "Net-(D21-K)") (class "Default")
      (node (ref "D21") (pin "C") (pinfunction "K_C") (pintype "passive"))
      (node (ref "LED20") (pin "+") (pinfunction "+_+") (pintype "passive"))
    )
    (net (code "117") (name "Net-(D21-PadA)") (class "Default")
      (node (ref "D21") (pin "A") (pinfunction "A_A") (pintype "passive"))
      (node (ref "R20") (pin "2") (pinfunction "2_2") (pintype "passive"))
    )
    (net (code "118") (name "Net-(D22-K)") (class "Default")
      (node (ref "D22") (pin "C") (pinfunction "K_C") (pintype "passive"))
      (node (ref "LED21") (pin "+") (pinfunction "+_+") (pintype "passive"))
    )
    (net (code "119") (name "Net-(D22-PadA)") (class "Default")
      (node (ref "D22") (pin "A") (pinfunction "A_A") (pintype "passive"))
      (node (ref "R21") (pin "2") (pinfunction "2_2") (pintype "passive"))
    )
    (net (code "120") (name "Net-(D23-K)") (class "Default")
      (node (ref "D23") (pin "C") (pinfunction "K_C") (pintype "passive"))
      (node (ref "LED22") (pin "+") (pinfunction "+_+") (pintype "passive"))
    )
    (net (code "121") (name "Net-(D23-PadA)") (class "Default")
      (node (ref "D23") (pin "A") (pinfunction "A_A") (pintype "passive"))
      (node (ref "R22") (pin "2") (pinfunction "2_2") (pintype "passive"))
    )
    (net (code "122") (name "Net-(D24-K)") (class "Default")
      (node (ref "D24") (pin "C") (pinfunction "K_C") (pintype "passive"))
      (node (ref "LED23") (pin "+") (pinfunction "+_+") (pintype "passive"))
    )
    (net (code "123") (name "Net-(D24-PadA)") (class "Default")
      (node (ref "D24") (pin "A") (pinfunction "A_A") (pintype "passive"))
      (node (ref "R23") (pin "2") (pinfunction "2_2") (pintype "passive"))
    )
    (net (code "124") (name "Net-(D25-K)") (class "Default")
      (node (ref "D25") (pin "C") (pinfunction "K_C") (pintype "passive"))
      (node (ref "LED24") (pin "+") (pinfunction "+_+") (pintype "passive"))
    )
    (net (code "125") (name "Net-(D25-PadA)") (class "Default")
      (node (ref "D25") (pin "A") (pinfunction "A_A") (pintype "passive"))
      (node (ref "R24") (pin "2") (pinfunction "2_2") (pintype "passive"))
    )
    (net (code "126") (name "Net-(D26-K)") (class "Default")
      (node (ref "D26") (pin "C") (pinfunction "K_C") (pintype "passive"))
      (node (ref "LED25") (pin "+") (pinfunction "+_+") (pintype "passive"))
    )
    (net (code "127") (name "Net-(D26-PadA)") (class "Default")
      (node (ref "D26") (pin "A") (pinfunction "A_A") (pintype "passive"))
      (node (ref "R25") (pin "2") (pinfunction "2_2") (pintype "passive"))
    )
    (net (code "128") (name "Net-(D27-K)") (class "Default")
      (node (ref "D27") (pin "C") (pinfunction "K_C") (pintype "passive"))
      (node (ref "LED26") (pin "+") (pinfunction "+_+") (pintype "passive"))
    )
    (net (code "129") (name "Net-(D27-PadA)") (class "Default")
      (node (ref "D27") (pin "A") (pinfunction "A_A") (pintype "passive"))
      (node (ref "R26") (pin "2") (pinfunction "2_2") (pintype "passive"))
    )
    (net (code "130") (name "Net-(D28-K)") (class "Default")
      (node (ref "D28") (pin "C") (pinfunction "K_C") (pintype "passive"))
      (node (ref "LED27") (pin "+") (pinfunction "+_+") (pintype "passive"))
    )
    (net (code "131") (name "Net-(D28-PadA)") (class "Default")
      (node (ref "D28") (pin "A") (pinfunction "A_A") (pintype "passive"))
      (node (ref "R27") (pin "2") (pinfunction "2_2") (pintype "passive"))
    )
    (net (code "132") (name "Net-(D29-K)") (class "Default")
      (node (ref "D29") (pin "C") (pinfunction "K_C") (pintype "passive"))
      (node (ref "LED28") (pin "+") (pinfunction "+_+") (pintype "passive"))
    )
    (net (code "133") (name "Net-(D29-PadA)") (class "Default")
      (node (ref "D29") (pin "A") (pinfunction "A_A") (pintype "passive"))
      (node (ref "R28") (pin "2") (pinfunction "2_2") (pintype "passive"))
    )
    (net (code "134") (name "Net-(D30-K)") (class "Default")
      (node (ref "D30") (pin "C") (pinfunction "K_C") (pintype "passive"))
      (node (ref "LED29") (pin "+") (pinfunction "+_+") (pintype "passive"))
    )
    (net (code "135") (name "Net-(D30-PadA)") (class "Default")
      (node (ref "D30") (pin "A") (pinfunction "A_A") (pintype "passive"))
      (node (ref "R29") (pin "2") (pinfunction "2_2") (pintype "passive"))
    )
    (net (code "136") (name "Net-(D31-K)") (class "Default")
      (node (ref "D31") (pin "C") (pinfunction "K_C") (pintype "passive"))
      (node (ref "LED30") (pin "+") (pinfunction "+_+") (pintype "passive"))
    )
    (net (code "137") (name "Net-(D31-PadA)") (class "Default")
      (node (ref "D31") (pin "A") (pinfunction "A_A") (pintype "passive"))
      (node (ref "R30") (pin "2") (pinfunction "2_2") (pintype "passive"))
    )
    (net (code "138") (name "Net-(D32-K)") (class "Default")
      (node (ref "D32") (pin "C") (pinfunction "K_C") (pintype "passive"))
      (node (ref "LED31") (pin "+") (pinfunction "+_+") (pintype "passive"))
    )
    (net (code "139") (name "Net-(D32-PadA)") (class "Default")
      (node (ref "D32") (pin "A") (pinfunction "A_A") (pintype "passive"))
      (node (ref "R31") (pin "2") (pinfunction "2_2") (pintype "passive"))
    )
    (net (code "140") (name "Net-(D33-K)") (class "Default")
      (node (ref "D33") (pin "C") (pinfunction "K_C") (pintype "passive"))
      (node (ref "LED32") (pin "+") (pinfunction "+_+") (pintype "passive"))
    )
    (net (code "141") (name "Net-(D33-PadA)") (class "Default")
      (node (ref "D33") (pin "A") (pinfunction "A_A") (pintype "passive"))
      (node (ref "R32") (pin "2") (pinfunction "2_2") (pintype "passive"))
    )
    (net (code "142") (name "Net-(IC1-A0)") (class "Default")
      (node (ref "IC1") (pin "15") (pinfunction "A0_15") (pintype "input"))
      (node (ref "R108") (pin "2") (pinfunction "2_2") (pintype "passive"))
    )
    (net (code "143") (name "Net-(IC1-A1)") (class "Default")
      (node (ref "IC1") (pin "16") (pinfunction "A1_16") (pintype "input"))
      (node (ref "R109") (pin "2") (pinfunction "2_2") (pintype "passive"))
    )
    (net (code "144") (name "Net-(IC1-A2)") (class "Default")
      (node (ref "IC1") (pin "17") (pinfunction "A2_17") (pintype "input"))
      (node (ref "R110") (pin "2") (pinfunction "2_2") (pintype "passive"))
    )
    (net (code "145") (name "Net-(IC1-~{RESET})") (class "Default")
      (node (ref "IC1") (pin "18") (pinfunction "~{RESET}_18") (pintype "input"))
      (node (ref "R107") (pin "1") (pinfunction "1_1") (pintype "passive"))
    )
    (net (code "146") (name "Net-(IC4-A0)") (class "Default")
      (node (ref "IC4") (pin "15") (pinfunction "A0_15") (pintype "input"))
      (node (ref "R106") (pin "2") (pinfunction "2_2") (pintype "passive"))
    )
    (net (code "147") (name "Net-(IC4-A1)") (class "Default")
      (node (ref "IC4") (pin "16") (pinfunction "A1_16") (pintype "input"))
      (node (ref "R105") (pin "2") (pinfunction "2_2") (pintype "passive"))
    )
    (net (code "148") (name "Net-(IC4-A2)") (class "Default")
      (node (ref "IC4") (pin "17") (pinfunction "A2_17") (pintype "input"))
      (node (ref "R104") (pin "2") (pinfunction "2_2") (pintype "passive"))
    )
    (net (code "149") (name "Net-(IC4-~{RESET})") (class "Default")
      (node (ref "IC4") (pin "18") (pinfunction "~{RESET}_18") (pintype "input"))
      (node (ref "R103") (pin "2") (pinfunction "2_2") (pintype "passive"))
    )
    (net (code "150") (name "Net-(JP3-1)") (class "Default")
      (node (ref "HEADER-22P1") (pin "21") (pinfunction "21_21") (pintype "bidirectional"))
      (node (ref "JP3") (pin "P$1") (pinfunction "1_P$1") (pintype "passive"))
    )
    (net (code "151") (name "Net-(K2A-2)") (class "Default")
      (node (ref "D34") (pin "A") (pinfunction "A_A") (pintype "passive"))
      (node (ref "K2") (pin "16") (pinfunction "2_16") (pintype "passive"))
      (node (ref "Q2") (pin "3") (pinfunction "C_3") (pintype "passive"))
    )
    (net (code "152") (name "Net-(K3A-2)") (class "Default")
      (node (ref "D36") (pin "A") (pinfunction "A_A") (pintype "passive"))
      (node (ref "K3") (pin "16") (pinfunction "2_16") (pintype "passive"))
      (node (ref "Q3") (pin "3") (pinfunction "C_3") (pintype "passive"))
    )
    (net (code "153") (name "Net-(K4A-2)") (class "Default")
      (node (ref "D38") (pin "A") (pinfunction "A_A") (pintype "passive"))
      (node (ref "K4") (pin "16") (pinfunction "2_16") (pintype "passive"))
      (node (ref "Q4") (pin "3") (pinfunction "C_3") (pintype "passive"))
    )
    (net (code "154") (name "Net-(K5A-2)") (class "Default")
      (node (ref "D40") (pin "A") (pinfunction "A_A") (pintype "passive"))
      (node (ref "K5") (pin "16") (pinfunction "2_16") (pintype "passive"))
      (node (ref "Q5") (pin "3") (pinfunction "C_3") (pintype "passive"))
    )
    (net (code "155") (name "Net-(K6A-2)") (class "Default")
      (node (ref "D42") (pin "A") (pinfunction "A_A") (pintype "passive"))
      (node (ref "K6") (pin "16") (pinfunction "2_16") (pintype "passive"))
      (node (ref "Q6") (pin "3") (pinfunction "C_3") (pintype "passive"))
    )
    (net (code "156") (name "Net-(K7A-2)") (class "Default")
      (node (ref "D44") (pin "A") (pinfunction "A_A") (pintype "passive"))
      (node (ref "K7") (pin "16") (pinfunction "2_16") (pintype "passive"))
      (node (ref "Q7") (pin "3") (pinfunction "C_3") (pintype "passive"))
    )
    (net (code "157") (name "Net-(K8A-2)") (class "Default")
      (node (ref "D46") (pin "A") (pinfunction "A_A") (pintype "passive"))
      (node (ref "K8") (pin "16") (pinfunction "2_16") (pintype "passive"))
      (node (ref "Q8") (pin "3") (pinfunction "C_3") (pintype "passive"))
    )
    (net (code "158") (name "Net-(K9A-2)") (class "Default")
      (node (ref "D48") (pin "A") (pinfunction "A_A") (pintype "passive"))
      (node (ref "K9") (pin "16") (pinfunction "2_16") (pintype "passive"))
      (node (ref "Q9") (pin "3") (pinfunction "C_3") (pintype "passive"))
    )
    (net (code "159") (name "Net-(OPTO1-A)") (class "Default")
      (node (ref "LED1") (pin "-") (pinfunction "-_-") (pintype "passive"))
      (node (ref "OPTO1") (pin "1") (pinfunction "A_1") (pintype "passive"))
      (node (ref "Z1") (pin "C") (pinfunction "C_C") (pintype "passive"))
    )
    (net (code "160") (name "Net-(OPTO2-A)") (class "Default")
      (node (ref "LED2") (pin "-") (pinfunction "-_-") (pintype "passive"))
      (node (ref "OPTO2") (pin "1") (pinfunction "A_1") (pintype "passive"))
      (node (ref "Z2") (pin "C") (pinfunction "C_C") (pintype "passive"))
    )
    (net (code "161") (name "Net-(OPTO3-A)") (class "Default")
      (node (ref "LED3") (pin "-") (pinfunction "-_-") (pintype "passive"))
      (node (ref "OPTO3") (pin "1") (pinfunction "A_1") (pintype "passive"))
      (node (ref "Z3") (pin "C") (pinfunction "C_C") (pintype "passive"))
    )
    (net (code "162") (name "Net-(OPTO4-A)") (class "Default")
      (node (ref "LED4") (pin "-") (pinfunction "-_-") (pintype "passive"))
      (node (ref "OPTO4") (pin "1") (pinfunction "A_1") (pintype "passive"))
      (node (ref "Z4") (pin "C") (pinfunction "C_C") (pintype "passive"))
    )
    (net (code "163") (name "Net-(OPTO5-A)") (class "Default")
      (node (ref "LED5") (pin "-") (pinfunction "-_-") (pintype "passive"))
      (node (ref "OPTO5") (pin "1") (pinfunction "A_1") (pintype "passive"))
      (node (ref "Z5") (pin "C") (pinfunction "C_C") (pintype "passive"))
    )
    (net (code "164") (name "Net-(OPTO6-A)") (class "Default")
      (node (ref "LED6") (pin "-") (pinfunction "-_-") (pintype "passive"))
      (node (ref "OPTO6") (pin "1") (pinfunction "A_1") (pintype "passive"))
      (node (ref "Z6") (pin "C") (pinfunction "C_C") (pintype "passive"))
    )
    (net (code "165") (name "Net-(OPTO7-A)") (class "Default")
      (node (ref "LED7") (pin "-") (pinfunction "-_-") (pintype "passive"))
      (node (ref "OPTO7") (pin "1") (pinfunction "A_1") (pintype "passive"))
      (node (ref "Z7") (pin "C") (pinfunction "C_C") (pintype "passive"))
    )
    (net (code "166") (name "Net-(OPTO8-A)") (class "Default")
      (node (ref "LED8") (pin "-") (pinfunction "-_-") (pintype "passive"))
      (node (ref "OPTO8") (pin "1") (pinfunction "A_1") (pintype "passive"))
      (node (ref "Z8") (pin "C") (pinfunction "C_C") (pintype "passive"))
    )
    (net (code "167") (name "Net-(OPTO9-A)") (class "Default")
      (node (ref "LED9") (pin "-") (pinfunction "-_-") (pintype "passive"))
      (node (ref "OPTO9") (pin "1") (pinfunction "A_1") (pintype "passive"))
      (node (ref "Z9") (pin "C") (pinfunction "C_C") (pintype "passive"))
    )
    (net (code "168") (name "Net-(OPTO10-A)") (class "Default")
      (node (ref "LED10") (pin "-") (pinfunction "-_-") (pintype "passive"))
      (node (ref "OPTO10") (pin "1") (pinfunction "A_1") (pintype "passive"))
      (node (ref "Z10") (pin "C") (pinfunction "C_C") (pintype "passive"))
    )
    (net (code "169") (name "Net-(OPTO11-A)") (class "Default")
      (node (ref "LED11") (pin "-") (pinfunction "-_-") (pintype "passive"))
      (node (ref "OPTO11") (pin "1") (pinfunction "A_1") (pintype "passive"))
      (node (ref "Z11") (pin "C") (pinfunction "C_C") (pintype "passive"))
    )
    (net (code "170") (name "Net-(OPTO12-A)") (class "Default")
      (node (ref "LED12") (pin "-") (pinfunction "-_-") (pintype "passive"))
      (node (ref "OPTO12") (pin "1") (pinfunction "A_1") (pintype "passive"))
      (node (ref "Z12") (pin "C") (pinfunction "C_C") (pintype "passive"))
    )
    (net (code "171") (name "Net-(OPTO13-A)") (class "Default")
      (node (ref "LED13") (pin "-") (pinfunction "-_-") (pintype "passive"))
      (node (ref "OPTO13") (pin "1") (pinfunction "A_1") (pintype "passive"))
      (node (ref "Z13") (pin "C") (pinfunction "C_C") (pintype "passive"))
    )
    (net (code "172") (name "Net-(OPTO14-A)") (class "Default")
      (node (ref "LED14") (pin "-") (pinfunction "-_-") (pintype "passive"))
      (node (ref "OPTO14") (pin "1") (pinfunction "A_1") (pintype "passive"))
      (node (ref "Z14") (pin "C") (pinfunction "C_C") (pintype "passive"))
    )
    (net (code "173") (name "Net-(OPTO15-A)") (class "Default")
      (node (ref "LED15") (pin "-") (pinfunction "-_-") (pintype "passive"))
      (node (ref "OPTO15") (pin "1") (pinfunction "A_1") (pintype "passive"))
      (node (ref "Z15") (pin "C") (pinfunction "C_C") (pintype "passive"))
    )
    (net (code "174") (name "Net-(OPTO16-A)") (class "Default")
      (node (ref "LED16") (pin "-") (pinfunction "-_-") (pintype "passive"))
      (node (ref "OPTO16") (pin "1") (pinfunction "A_1") (pintype "passive"))
      (node (ref "Z16") (pin "C") (pinfunction "C_C") (pintype "passive"))
    )
    (net (code "175") (name "Net-(OPTO17-A)") (class "Default")
      (node (ref "LED17") (pin "-") (pinfunction "-_-") (pintype "passive"))
      (node (ref "OPTO17") (pin "1") (pinfunction "A_1") (pintype "passive"))
      (node (ref "Z17") (pin "C") (pinfunction "C_C") (pintype "passive"))
    )
    (net (code "176") (name "Net-(OPTO18-A)") (class "Default")
      (node (ref "LED18") (pin "-") (pinfunction "-_-") (pintype "passive"))
      (node (ref "OPTO18") (pin "1") (pinfunction "A_1") (pintype "passive"))
      (node (ref "Z18") (pin "C") (pinfunction "C_C") (pintype "passive"))
    )
    (net (code "177") (name "Net-(OPTO19-A)") (class "Default")
      (node (ref "LED19") (pin "-") (pinfunction "-_-") (pintype "passive"))
      (node (ref "OPTO19") (pin "1") (pinfunction "A_1") (pintype "passive"))
      (node (ref "Z19") (pin "C") (pinfunction "C_C") (pintype "passive"))
    )
    (net (code "178") (name "Net-(OPTO20-A)") (class "Default")
      (node (ref "LED20") (pin "-") (pinfunction "-_-") (pintype "passive"))
      (node (ref "OPTO20") (pin "1") (pinfunction "A_1") (pintype "passive"))
      (node (ref "Z20") (pin "C") (pinfunction "C_C") (pintype "passive"))
    )
    (net (code "179") (name "Net-(OPTO21-A)") (class "Default")
      (node (ref "LED21") (pin "-") (pinfunction "-_-") (pintype "passive"))
      (node (ref "OPTO21") (pin "1") (pinfunction "A_1") (pintype "passive"))
      (node (ref "Z21") (pin "C") (pinfunction "C_C") (pintype "passive"))
    )
    (net (code "180") (name "Net-(OPTO22-A)") (class "Default")
      (node (ref "LED22") (pin "-") (pinfunction "-_-") (pintype "passive"))
      (node (ref "OPTO22") (pin "1") (pinfunction "A_1") (pintype "passive"))
      (node (ref "Z22") (pin "C") (pinfunction "C_C") (pintype "passive"))
    )
    (net (code "181") (name "Net-(OPTO23-A)") (class "Default")
      (node (ref "LED23") (pin "-") (pinfunction "-_-") (pintype "passive"))
      (node (ref "OPTO23") (pin "1") (pinfunction "A_1") (pintype "passive"))
      (node (ref "Z23") (pin "C") (pinfunction "C_C") (pintype "passive"))
    )
    (net (code "182") (name "Net-(OPTO24-A)") (class "Default")
      (node (ref "LED24") (pin "-") (pinfunction "-_-") (pintype "passive"))
      (node (ref "OPTO24") (pin "1") (pinfunction "A_1") (pintype "passive"))
      (node (ref "Z24") (pin "C") (pinfunction "C_C") (pintype "passive"))
    )
    (net (code "183") (name "Net-(OPTO25-A)") (class "Default")
      (node (ref "LED25") (pin "-") (pinfunction "-_-") (pintype "passive"))
      (node (ref "OPTO25") (pin "1") (pinfunction "A_1") (pintype "passive"))
      (node (ref "Z25") (pin "C") (pinfunction "C_C") (pintype "passive"))
    )
    (net (code "184") (name "Net-(OPTO26-A)") (class "Default")
      (node (ref "LED26") (pin "-") (pinfunction "-_-") (pintype "passive"))
      (node (ref "OPTO26") (pin "1") (pinfunction "A_1") (pintype "passive"))
      (node (ref "Z26") (pin "C") (pinfunction "C_C") (pintype "passive"))
    )
    (net (code "185") (name "Net-(OPTO27-A)") (class "Default")
      (node (ref "LED27") (pin "-") (pinfunction "-_-") (pintype "passive"))
      (node (ref "OPTO27") (pin "1") (pinfunction "A_1") (pintype "passive"))
      (node (ref "Z27") (pin "C") (pinfunction "C_C") (pintype "passive"))
    )
    (net (code "186") (name "Net-(OPTO28-A)") (class "Default")
      (node (ref "LED28") (pin "-") (pinfunction "-_-") (pintype "passive"))
      (node (ref "OPTO28") (pin "1") (pinfunction "A_1") (pintype "passive"))
      (node (ref "Z28") (pin "C") (pinfunction "C_C") (pintype "passive"))
    )
    (net (code "187") (name "Net-(OPTO29-A)") (class "Default")
      (node (ref "LED29") (pin "-") (pinfunction "-_-") (pintype "passive"))
      (node (ref "OPTO29") (pin "1") (pinfunction "A_1") (pintype "passive"))
      (node (ref "Z29") (pin "C") (pinfunction "C_C") (pintype "passive"))
    )
    (net (code "188") (name "Net-(OPTO30-A)") (class "Default")
      (node (ref "LED30") (pin "-") (pinfunction "-_-") (pintype "passive"))
      (node (ref "OPTO30") (pin "1") (pinfunction "A_1") (pintype "passive"))
      (node (ref "Z30") (pin "C") (pinfunction "C_C") (pintype "passive"))
    )
    (net (code "189") (name "Net-(OPTO31-A)") (class "Default")
      (node (ref "LED31") (pin "-") (pinfunction "-_-") (pintype "passive"))
      (node (ref "OPTO31") (pin "1") (pinfunction "A_1") (pintype "passive"))
      (node (ref "Z31") (pin "C") (pinfunction "C_C") (pintype "passive"))
    )
    (net (code "190") (name "Net-(OPTO32-A)") (class "Default")
      (node (ref "LED32") (pin "-") (pinfunction "-_-") (pintype "passive"))
      (node (ref "OPTO32") (pin "1") (pinfunction "A_1") (pintype "passive"))
      (node (ref "Z32") (pin "C") (pinfunction "C_C") (pintype "passive"))
    )
    (net (code "191") (name "Net-(Q2-B)") (class "Default")
      (node (ref "Q2") (pin "1") (pinfunction "B_1") (pintype "passive"))
      (node (ref "U1") (pin "3") (pinfunction "ET_3") (pintype "passive"))
    )
    (net (code "192") (name "Net-(Q3-B)") (class "Default")
      (node (ref "Q3") (pin "1") (pinfunction "B_1") (pintype "passive"))
      (node (ref "U2") (pin "3") (pinfunction "ET_3") (pintype "passive"))
    )
    (net (code "193") (name "Net-(Q4-B)") (class "Default")
      (node (ref "Q4") (pin "1") (pinfunction "B_1") (pintype "passive"))
      (node (ref "U3") (pin "3") (pinfunction "ET_3") (pintype "passive"))
    )
    (net (code "194") (name "Net-(Q5-B)") (class "Default")
      (node (ref "Q5") (pin "1") (pinfunction "B_1") (pintype "passive"))
      (node (ref "U4") (pin "3") (pinfunction "ET_3") (pintype "passive"))
    )
    (net (code "195") (name "Net-(Q6-B)") (class "Default")
      (node (ref "Q6") (pin "1") (pinfunction "B_1") (pintype "passive"))
      (node (ref "U5") (pin "3") (pinfunction "ET_3") (pintype "passive"))
    )
    (net (code "196") (name "Net-(Q7-B)") (class "Default")
      (node (ref "Q7") (pin "1") (pinfunction "B_1") (pintype "passive"))
      (node (ref "U6") (pin "3") (pinfunction "ET_3") (pintype "passive"))
    )
    (net (code "197") (name "Net-(Q8-B)") (class "Default")
      (node (ref "Q8") (pin "1") (pinfunction "B_1") (pintype "passive"))
      (node (ref "U7") (pin "3") (pinfunction "ET_3") (pintype "passive"))
    )
    (net (code "198") (name "Net-(Q9-B)") (class "Default")
      (node (ref "Q9") (pin "1") (pinfunction "B_1") (pintype "passive"))
      (node (ref "U8") (pin "3") (pinfunction "ET_3") (pintype "passive"))
    )
    (net (code "199") (name "Net-(U1-A)") (class "Default")
      (node (ref "R34") (pin "1") (pinfunction "1_1") (pintype "passive"))
      (node (ref "U1") (pin "1") (pinfunction "A_1") (pintype "passive"))
    )
    (net (code "200") (name "Net-(U1-CT)") (class "Default")
      (node (ref "R33") (pin "1") (pinfunction "1_1") (pintype "passive"))
      (node (ref "U1") (pin "4") (pinfunction "CT_4") (pintype "passive"))
    )
    (net (code "201") (name "Net-(U2-A)") (class "Default")
      (node (ref "R36") (pin "1") (pinfunction "1_1") (pintype "passive"))
      (node (ref "U2") (pin "1") (pinfunction "A_1") (pintype "passive"))
    )
    (net (code "202") (name "Net-(U2-CT)") (class "Default")
      (node (ref "R35") (pin "1") (pinfunction "1_1") (pintype "passive"))
      (node (ref "U2") (pin "4") (pinfunction "CT_4") (pintype "passive"))
    )
    (net (code "203") (name "Net-(U3-A)") (class "Default")
      (node (ref "R38") (pin "1") (pinfunction "1_1") (pintype "passive"))
      (node (ref "U3") (pin "1") (pinfunction "A_1") (pintype "passive"))
    )
    (net (code "204") (name "Net-(U3-CT)") (class "Default")
      (node (ref "R37") (pin "1") (pinfunction "1_1") (pintype "passive"))
      (node (ref "U3") (pin "4") (pinfunction "CT_4") (pintype "passive"))
    )
    (net (code "205") (name "Net-(U4-A)") (class "Default")
      (node (ref "R40") (pin "1") (pinfunction "1_1") (pintype "passive"))
      (node (ref "U4") (pin "1") (pinfunction "A_1") (pintype "passive"))
    )
    (net (code "206") (name "Net-(U4-CT)") (class "Default")
      (node (ref "R39") (pin "1") (pinfunction "1_1") (pintype "passive"))
      (node (ref "U4") (pin "4") (pinfunction "CT_4") (pintype "passive"))
    )
    (net (code "207") (name "Net-(U5-A)") (class "Default")
      (node (ref "R42") (pin "1") (pinfunction "1_1") (pintype "passive"))
      (node (ref "U5") (pin "1") (pinfunction "A_1") (pintype "passive"))
    )
    (net (code "208") (name "Net-(U5-CT)") (class "Default")
      (node (ref "R41") (pin "1") (pinfunction "1_1") (pintype "passive"))
      (node (ref "U5") (pin "4") (pinfunction "CT_4") (pintype "passive"))
    )
    (net (code "209") (name "Net-(U6-A)") (class "Default")
      (node (ref "R44") (pin "1") (pinfunction "1_1") (pintype "passive"))
      (node (ref "U6") (pin "1") (pinfunction "A_1") (pintype "passive"))
    )
    (net (code "210") (name "Net-(U6-CT)") (class "Default")
      (node (ref "R43") (pin "1") (pinfunction "1_1") (pintype "passive"))
      (node (ref "U6") (pin "4") (pinfunction "CT_4") (pintype "passive"))
    )
    (net (code "211") (name "Net-(U7-A)") (class "Default")
      (node (ref "R46") (pin "1") (pinfunction "1_1") (pintype "passive"))
      (node (ref "U7") (pin "1") (pinfunction "A_1") (pintype "passive"))
    )
    (net (code "212") (name "Net-(U7-CT)") (class "Default")
      (node (ref "R45") (pin "1") (pinfunction "1_1") (pintype "passive"))
      (node (ref "U7") (pin "4") (pinfunction "CT_4") (pintype "passive"))
    )
    (net (code "213") (name "Net-(U8-A)") (class "Default")
      (node (ref "R48") (pin "1") (pinfunction "1_1") (pintype "passive"))
      (node (ref "U8") (pin "1") (pinfunction "A_1") (pintype "passive"))
    )
    (net (code "214") (name "Net-(U8-CT)") (class "Default")
      (node (ref "R47") (pin "1") (pinfunction "1_1") (pintype "passive"))
      (node (ref "U8") (pin "4") (pinfunction "CT_4") (pintype "passive"))
    )
    (net (code "215") (name "PDO1") (class "Default")
      (node (ref "HEADER-22P1") (pin "4") (pinfunction "4_4") (pintype "bidirectional"))
      (node (ref "K2") (pin "P1") (pinfunction "P_P1") (pintype "passive"))
    )
    (net (code "216") (name "PDO2") (class "Default")
      (node (ref "HEADER-22P1") (pin "5") (pinfunction "5_5") (pintype "bidirectional"))
      (node (ref "K3") (pin "P1") (pinfunction "P_P1") (pintype "passive"))
    )
    (net (code "217") (name "PDO3") (class "Default")
      (node (ref "HEADER-22P1") (pin "6") (pinfunction "6_6") (pintype "bidirectional"))
      (node (ref "K4") (pin "P1") (pinfunction "P_P1") (pintype "passive"))
    )
    (net (code "218") (name "PDO4") (class "Default")
      (node (ref "HEADER-22P1") (pin "7") (pinfunction "7_7") (pintype "bidirectional"))
      (node (ref "K5") (pin "P1") (pinfunction "P_P1") (pintype "passive"))
    )
    (net (code "219") (name "PDO5") (class "Default")
      (node (ref "HEADER-22P1") (pin "8") (pinfunction "8_8") (pintype "bidirectional"))
      (node (ref "K6") (pin "P1") (pinfunction "P_P1") (pintype "passive"))
    )
    (net (code "220") (name "PDO6") (class "Default")
      (node (ref "HEADER-22P1") (pin "9") (pinfunction "9_9") (pintype "bidirectional"))
      (node (ref "K7") (pin "P1") (pinfunction "P_P1") (pintype "passive"))
    )
    (net (code "221") (name "PDO7") (class "Default")
      (node (ref "HEADER-22P1") (pin "10") (pinfunction "10_10") (pintype "bidirectional"))
      (node (ref "K8") (pin "P1") (pinfunction "P_P1") (pintype "passive"))
    )
    (net (code "222") (name "PDO8") (class "Default")
      (node (ref "HEADER-22P1") (pin "11") (pinfunction "11_11") (pintype "bidirectional"))
      (node (ref "K9") (pin "P1") (pinfunction "P_P1") (pintype "passive"))
    )
    (net (code "223") (name "RS_A") (class "Default")
      (node (ref "JP2") (pin "12") (pinfunction "12_12") (pintype "passive"))
      (node (ref "USB2RS1") (pin "A") (pinfunction "A_A") (pintype "bidirectional"))
    )
    (net (code "224") (name "RS_B") (class "Default")
      (node (ref "JP2") (pin "10") (pinfunction "10_10") (pintype "passive"))
      (node (ref "USB2RS1") (pin "B") (pinfunction "B_B") (pintype "bidirectional"))
    )
    (net (code "225") (name "RX") (class "Default")
      (node (ref "JP2") (pin "3") (pinfunction "3_3") (pintype "passive"))
      (node (ref "TTL-RS1") (pin "RX") (pinfunction "RX_RX") (pintype "bidirectional"))
    )
    (net (code "226") (name "SCL") (class "Default")
      (node (ref "IC1") (pin "12") (pinfunction "SCL_12") (pintype "input"))
      (node (ref "IC4") (pin "12") (pinfunction "SCL_12") (pintype "input"))
      (node (ref "JP2") (pin "9") (pinfunction "9_9") (pintype "passive"))
      (node (ref "R97") (pin "1") (pinfunction "1_1") (pintype "passive"))
      (node (ref "R99") (pin "1") (pinfunction "1_1") (pintype "passive"))
    )
    (net (code "227") (name "SDA") (class "Default")
      (node (ref "IC1") (pin "13") (pinfunction "SDA_13") (pintype "bidirectional"))
      (node (ref "IC4") (pin "13") (pinfunction "SDA_13") (pintype "bidirectional"))
      (node (ref "JP2") (pin "11") (pinfunction "11_11") (pintype "passive"))
      (node (ref "R100") (pin "1") (pinfunction "1_1") (pintype "passive"))
      (node (ref "R98") (pin "1") (pinfunction "1_1") (pintype "passive"))
    )
    (net (code "228") (name "TX") (class "Default")
      (node (ref "JP2") (pin "1") (pinfunction "1_1") (pintype "passive"))
      (node (ref "TTL-RS1") (pin "TX") (pinfunction "TX_TX") (pintype "bidirectional"))
    )
    (net (code "229") (name "USBRS_D+") (class "Default")
      (node (ref "JP2") (pin "8") (pinfunction "8_8") (pintype "passive"))
      (node (ref "USB2RS1") (pin "3") (pinfunction "3_3") (pintype "bidirectional"))
    )
    (net (code "230") (name "USBRS_D-") (class "Default")
      (node (ref "JP2") (pin "6") (pinfunction "6_6") (pintype "passive"))
      (node (ref "USB2RS1") (pin "2") (pinfunction "2_2") (pintype "bidirectional"))
    )
    (net (code "231") (name "VCC") (class "Default")
      (node (ref "D34") (pin "C") (pinfunction "K_C") (pintype "passive"))
      (node (ref "D36") (pin "C") (pinfunction "K_C") (pintype "passive"))
      (node (ref "D38") (pin "C") (pinfunction "K_C") (pintype "passive"))
      (node (ref "D40") (pin "C") (pinfunction "K_C") (pintype "passive"))
      (node (ref "D42") (pin "C") (pinfunction "K_C") (pintype "passive"))
      (node (ref "D44") (pin "C") (pinfunction "K_C") (pintype "passive"))
      (node (ref "D46") (pin "C") (pinfunction "K_C") (pintype "passive"))
      (node (ref "D48") (pin "C") (pinfunction "K_C") (pintype "passive"))
      (node (ref "IC1") (pin "9") (pinfunction "VDD_9") (pintype "power_in"))
      (node (ref "IC4") (pin "9") (pinfunction "VDD_9") (pintype "power_in"))
      (node (ref "JP2") (pin "4") (pinfunction "4_4") (pintype "passive"))
      (node (ref "JP4") (pin "1") (pinfunction "1_1") (pintype "passive"))
      (node (ref "JP4") (pin "3") (pinfunction "3_3") (pintype "passive"))
      (node (ref "K2") (pin "1") (pinfunction "1_1") (pintype "passive"))
      (node (ref "K3") (pin "1") (pinfunction "1_1") (pintype "passive"))
      (node (ref "K4") (pin "1") (pinfunction "1_1") (pintype "passive"))
      (node (ref "K5") (pin "1") (pinfunction "1_1") (pintype "passive"))
      (node (ref "K6") (pin "1") (pinfunction "1_1") (pintype "passive"))
      (node (ref "K7") (pin "1") (pinfunction "1_1") (pintype "passive"))
      (node (ref "K8") (pin "1") (pinfunction "1_1") (pintype "passive"))
      (node (ref "K9") (pin "1") (pinfunction "1_1") (pintype "passive"))
      (node (ref "R100") (pin "2") (pinfunction "2_2") (pintype "passive"))
      (node (ref "R103") (pin "1") (pinfunction "1_1") (pintype "passive"))
      (node (ref "R107") (pin "2") (pinfunction "2_2") (pintype "passive"))
      (node (ref "R108") (pin "1") (pinfunction "1_1") (pintype "passive"))
      (node (ref "R33") (pin "2") (pinfunction "2_2") (pintype "passive"))
      (node (ref "R35") (pin "2") (pinfunction "2_2") (pintype "passive"))
      (node (ref "R37") (pin "2") (pinfunction "2_2") (pintype "passive"))
      (node (ref "R39") (pin "2") (pinfunction "2_2") (pintype "passive"))
      (node (ref "R41") (pin "2") (pinfunction "2_2") (pintype "passive"))
      (node (ref "R43") (pin "2") (pinfunction "2_2") (pintype "passive"))
      (node (ref "R45") (pin "2") (pinfunction "2_2") (pintype "passive"))
      (node (ref "R47") (pin "2") (pinfunction "2_2") (pintype "passive"))
      (node (ref "R49") (pin "2") (pinfunction "2_2") (pintype "passive"))
      (node (ref "R50") (pin "2") (pinfunction "2_2") (pintype "passive"))
      (node (ref "R51") (pin "2") (pinfunction "2_2") (pintype "passive"))
      (node (ref "R52") (pin "2") (pinfunction "2_2") (pintype "passive"))
      (node (ref "R53") (pin "2") (pinfunction "2_2") (pintype "passive"))
      (node (ref "R54") (pin "2") (pinfunction "2_2") (pintype "passive"))
      (node (ref "R55") (pin "2") (pinfunction "2_2") (pintype "passive"))
      (node (ref "R56") (pin "2") (pinfunction "2_2") (pintype "passive"))
      (node (ref "R57") (pin "2") (pinfunction "2_2") (pintype "passive"))
      (node (ref "R58") (pin "2") (pinfunction "2_2") (pintype "passive"))
      (node (ref "R59") (pin "2") (pinfunction "2_2") (pintype "passive"))
      (node (ref "R60") (pin "2") (pinfunction "2_2") (pintype "passive"))
      (node (ref "R61") (pin "2") (pinfunction "2_2") (pintype "passive"))
      (node (ref "R62") (pin "2") (pinfunction "2_2") (pintype "passive"))
      (node (ref "R63") (pin "2") (pinfunction "2_2") (pintype "passive"))
      (node (ref "R64") (pin "2") (pinfunction "2_2") (pintype "passive"))
      (node (ref "R65") (pin "2") (pinfunction "2_2") (pintype "passive"))
      (node (ref "R66") (pin "2") (pinfunction "2_2") (pintype "passive"))
      (node (ref "R67") (pin "2") (pinfunction "2_2") (pintype "passive"))
      (node (ref "R68") (pin "2") (pinfunction "2_2") (pintype "passive"))
      (node (ref "R69") (pin "2") (pinfunction "2_2") (pintype "passive"))
      (node (ref "R70") (pin "2") (pinfunction "2_2") (pintype "passive"))
      (node (ref "R71") (pin "2") (pinfunction "2_2") (pintype "passive"))
      (node (ref "R72") (pin "2") (pinfunction "2_2") (pintype "passive"))
      (node (ref "R73") (pin "2") (pinfunction "2_2") (pintype "passive"))
      (node (ref "R74") (pin "2") (pinfunction "2_2") (pintype "passive"))
      (node (ref "R75") (pin "2") (pinfunction "2_2") (pintype "passive"))
      (node (ref "R76") (pin "2") (pinfunction "2_2") (pintype "passive"))
      (node (ref "R77") (pin "2") (pinfunction "2_2") (pintype "passive"))
      (node (ref "R78") (pin "2") (pinfunction "2_2") (pintype "passive"))
      (node (ref "R79") (pin "2") (pinfunction "2_2") (pintype "passive"))
      (node (ref "R80") (pin "2") (pinfunction "2_2") (pintype "passive"))
      (node (ref "R97") (pin "2") (pinfunction "2_2") (pintype "passive"))
      (node (ref "R98") (pin "2") (pinfunction "2_2") (pintype "passive"))
      (node (ref "R99") (pin "2") (pinfunction "2_2") (pintype "passive"))
      (node (ref "TTL-RS1") (pin "VCC") (pinfunction "VCC_VCC") (pintype "bidirectional"))
      (node (ref "USB2RS1") (pin "1") (pinfunction "1_1") (pintype "bidirectional"))
    )
    (net (code "232") (name "unconnected-(HEADER-22P1-Pad12)") (class "Default")
      (node (ref "HEADER-22P1") (pin "12") (pinfunction "12_12") (pintype "bidirectional"))
    )
    (net (code "233") (name "unconnected-(HEADER-22P1-Pad13)") (class "Default")
      (node (ref "HEADER-22P1") (pin "13") (pinfunction "13_13") (pintype "bidirectional"))
    )
    (net (code "234") (name "unconnected-(HEADER-22P1-Pad14)") (class "Default")
      (node (ref "HEADER-22P1") (pin "14") (pinfunction "14_14") (pintype "bidirectional"))
    )
    (net (code "235") (name "unconnected-(HEADER-22P1-Pad15)") (class "Default")
      (node (ref "HEADER-22P1") (pin "15") (pinfunction "15_15") (pintype "bidirectional"))
    )
    (net (code "236") (name "unconnected-(HEADER-22P1-Pad16)") (class "Default")
      (node (ref "HEADER-22P1") (pin "16") (pinfunction "16_16") (pintype "bidirectional"))
    )
    (net (code "237") (name "unconnected-(HEADER-22P1-Pad17)") (class "Default")
      (node (ref "HEADER-22P1") (pin "17") (pinfunction "17_17") (pintype "bidirectional"))
    )
    (net (code "238") (name "unconnected-(HEADER-22P1-Pad18)") (class "Default")
      (node (ref "HEADER-22P1") (pin "18") (pinfunction "18_18") (pintype "bidirectional"))
    )
    (net (code "239") (name "unconnected-(HEADER-22P1-Pad19)") (class "Default")
      (node (ref "HEADER-22P1") (pin "19") (pinfunction "19_19") (pintype "bidirectional"))
    )
    (net (code "240") (name "unconnected-(IC1-INTA-Pad20)") (class "Default")
      (node (ref "IC1") (pin "20") (pinfunction "INTA_20") (pintype "output"))
    )
    (net (code "241") (name "unconnected-(IC1-INTB-Pad19)") (class "Default")
      (node (ref "IC1") (pin "19") (pinfunction "INTB_19") (pintype "output"))
    )
    (net (code "242") (name "unconnected-(IC4-INTA-Pad20)") (class "Default")
      (node (ref "IC4") (pin "20") (pinfunction "INTA_20") (pintype "output"))
    )
    (net (code "243") (name "unconnected-(IC4-INTB-Pad19)") (class "Default")
      (node (ref "IC4") (pin "19") (pinfunction "INTB_19") (pintype "output"))
    )
    (net (code "244") (name "unconnected-(K2B-O-PadO1)") (class "Default")
      (node (ref "K2") (pin "O1") (pinfunction "O_O1") (pintype "passive"))
    )
    (net (code "245") (name "unconnected-(K2C-O-PadO2)") (class "Default")
      (node (ref "K2") (pin "O2") (pinfunction "O_O2") (pintype "passive"))
    )
    (net (code "246") (name "unconnected-(K2C-P-PadP2)") (class "Default")
      (node (ref "K2") (pin "P2") (pinfunction "P_P2") (pintype "passive"))
    )
    (net (code "247") (name "unconnected-(K2C-S-PadS2)") (class "Default")
      (node (ref "K2") (pin "S2") (pinfunction "S_S2") (pintype "passive"))
    )
    (net (code "248") (name "unconnected-(K3B-O-PadO1)") (class "Default")
      (node (ref "K3") (pin "O1") (pinfunction "O_O1") (pintype "passive"))
    )
    (net (code "249") (name "unconnected-(K3C-O-PadO2)") (class "Default")
      (node (ref "K3") (pin "O2") (pinfunction "O_O2") (pintype "passive"))
    )
    (net (code "250") (name "unconnected-(K3C-P-PadP2)") (class "Default")
      (node (ref "K3") (pin "P2") (pinfunction "P_P2") (pintype "passive"))
    )
    (net (code "251") (name "unconnected-(K3C-S-PadS2)") (class "Default")
      (node (ref "K3") (pin "S2") (pinfunction "S_S2") (pintype "passive"))
    )
    (net (code "252") (name "unconnected-(K4B-O-PadO1)") (class "Default")
      (node (ref "K4") (pin "O1") (pinfunction "O_O1") (pintype "passive"))
    )
    (net (code "253") (name "unconnected-(K4C-O-PadO2)") (class "Default")
      (node (ref "K4") (pin "O2") (pinfunction "O_O2") (pintype "passive"))
    )
    (net (code "254") (name "unconnected-(K4C-P-PadP2)") (class "Default")
      (node (ref "K4") (pin "P2") (pinfunction "P_P2") (pintype "passive"))
    )
    (net (code "255") (name "unconnected-(K4C-S-PadS2)") (class "Default")
      (node (ref "K4") (pin "S2") (pinfunction "S_S2") (pintype "passive"))
    )
    (net (code "256") (name "unconnected-(K5B-O-PadO1)") (class "Default")
      (node (ref "K5") (pin "O1") (pinfunction "O_O1") (pintype "passive"))
    )
    (net (code "257") (name "unconnected-(K5C-O-PadO2)") (class "Default")
      (node (ref "K5") (pin "O2") (pinfunction "O_O2") (pintype "passive"))
    )
    (net (code "258") (name "unconnected-(K5C-P-PadP2)") (class "Default")
      (node (ref "K5") (pin "P2") (pinfunction "P_P2") (pintype "passive"))
    )
    (net (code "259") (name "unconnected-(K5C-S-PadS2)") (class "Default")
      (node (ref "K5") (pin "S2") (pinfunction "S_S2") (pintype "passive"))
    )
    (net (code "260") (name "unconnected-(K6B-O-PadO1)") (class "Default")
      (node (ref "K6") (pin "O1") (pinfunction "O_O1") (pintype "passive"))
    )
    (net (code "261") (name "unconnected-(K6C-O-PadO2)") (class "Default")
      (node (ref "K6") (pin "O2") (pinfunction "O_O2") (pintype "passive"))
    )
    (net (code "262") (name "unconnected-(K6C-P-PadP2)") (class "Default")
      (node (ref "K6") (pin "P2") (pinfunction "P_P2") (pintype "passive"))
    )
    (net (code "263") (name "unconnected-(K6C-S-PadS2)") (class "Default")
      (node (ref "K6") (pin "S2") (pinfunction "S_S2") (pintype "passive"))
    )
    (net (code "264") (name "unconnected-(K7B-O-PadO1)") (class "Default")
      (node (ref "K7") (pin "O1") (pinfunction "O_O1") (pintype "passive"))
    )
    (net (code "265") (name "unconnected-(K7C-O-PadO2)") (class "Default")
      (node (ref "K7") (pin "O2") (pinfunction "O_O2") (pintype "passive"))
    )
    (net (code "266") (name "unconnected-(K7C-P-PadP2)") (class "Default")
      (node (ref "K7") (pin "P2") (pinfunction "P_P2") (pintype "passive"))
    )
    (net (code "267") (name "unconnected-(K7C-S-PadS2)") (class "Default")
      (node (ref "K7") (pin "S2") (pinfunction "S_S2") (pintype "passive"))
    )
    (net (code "268") (name "unconnected-(K8B-O-PadO1)") (class "Default")
      (node (ref "K8") (pin "O1") (pinfunction "O_O1") (pintype "passive"))
    )
    (net (code "269") (name "unconnected-(K8C-O-PadO2)") (class "Default")
      (node (ref "K8") (pin "O2") (pinfunction "O_O2") (pintype "passive"))
    )
    (net (code "270") (name "unconnected-(K8C-P-PadP2)") (class "Default")
      (node (ref "K8") (pin "P2") (pinfunction "P_P2") (pintype "passive"))
    )
    (net (code "271") (name "unconnected-(K8C-S-PadS2)") (class "Default")
      (node (ref "K8") (pin "S2") (pinfunction "S_S2") (pintype "passive"))
    )
    (net (code "272") (name "unconnected-(K9B-O-PadO1)") (class "Default")
      (node (ref "K9") (pin "O1") (pinfunction "O_O1") (pintype "passive"))
    )
    (net (code "273") (name "unconnected-(K9C-O-PadO2)") (class "Default")
      (node (ref "K9") (pin "O2") (pinfunction "O_O2") (pintype "passive"))
    )
    (net (code "274") (name "unconnected-(K9C-P-PadP2)") (class "Default")
      (node (ref "K9") (pin "P2") (pinfunction "P_P2") (pintype "passive"))
    )
    (net (code "275") (name "unconnected-(K9C-S-PadS2)") (class "Default")
      (node (ref "K9") (pin "S2") (pinfunction "S_S2") (pintype "passive"))
    )
  )
)
